# sr42-revB-kbd.net
KiCad netlist of a schematic drawn in EAGLE
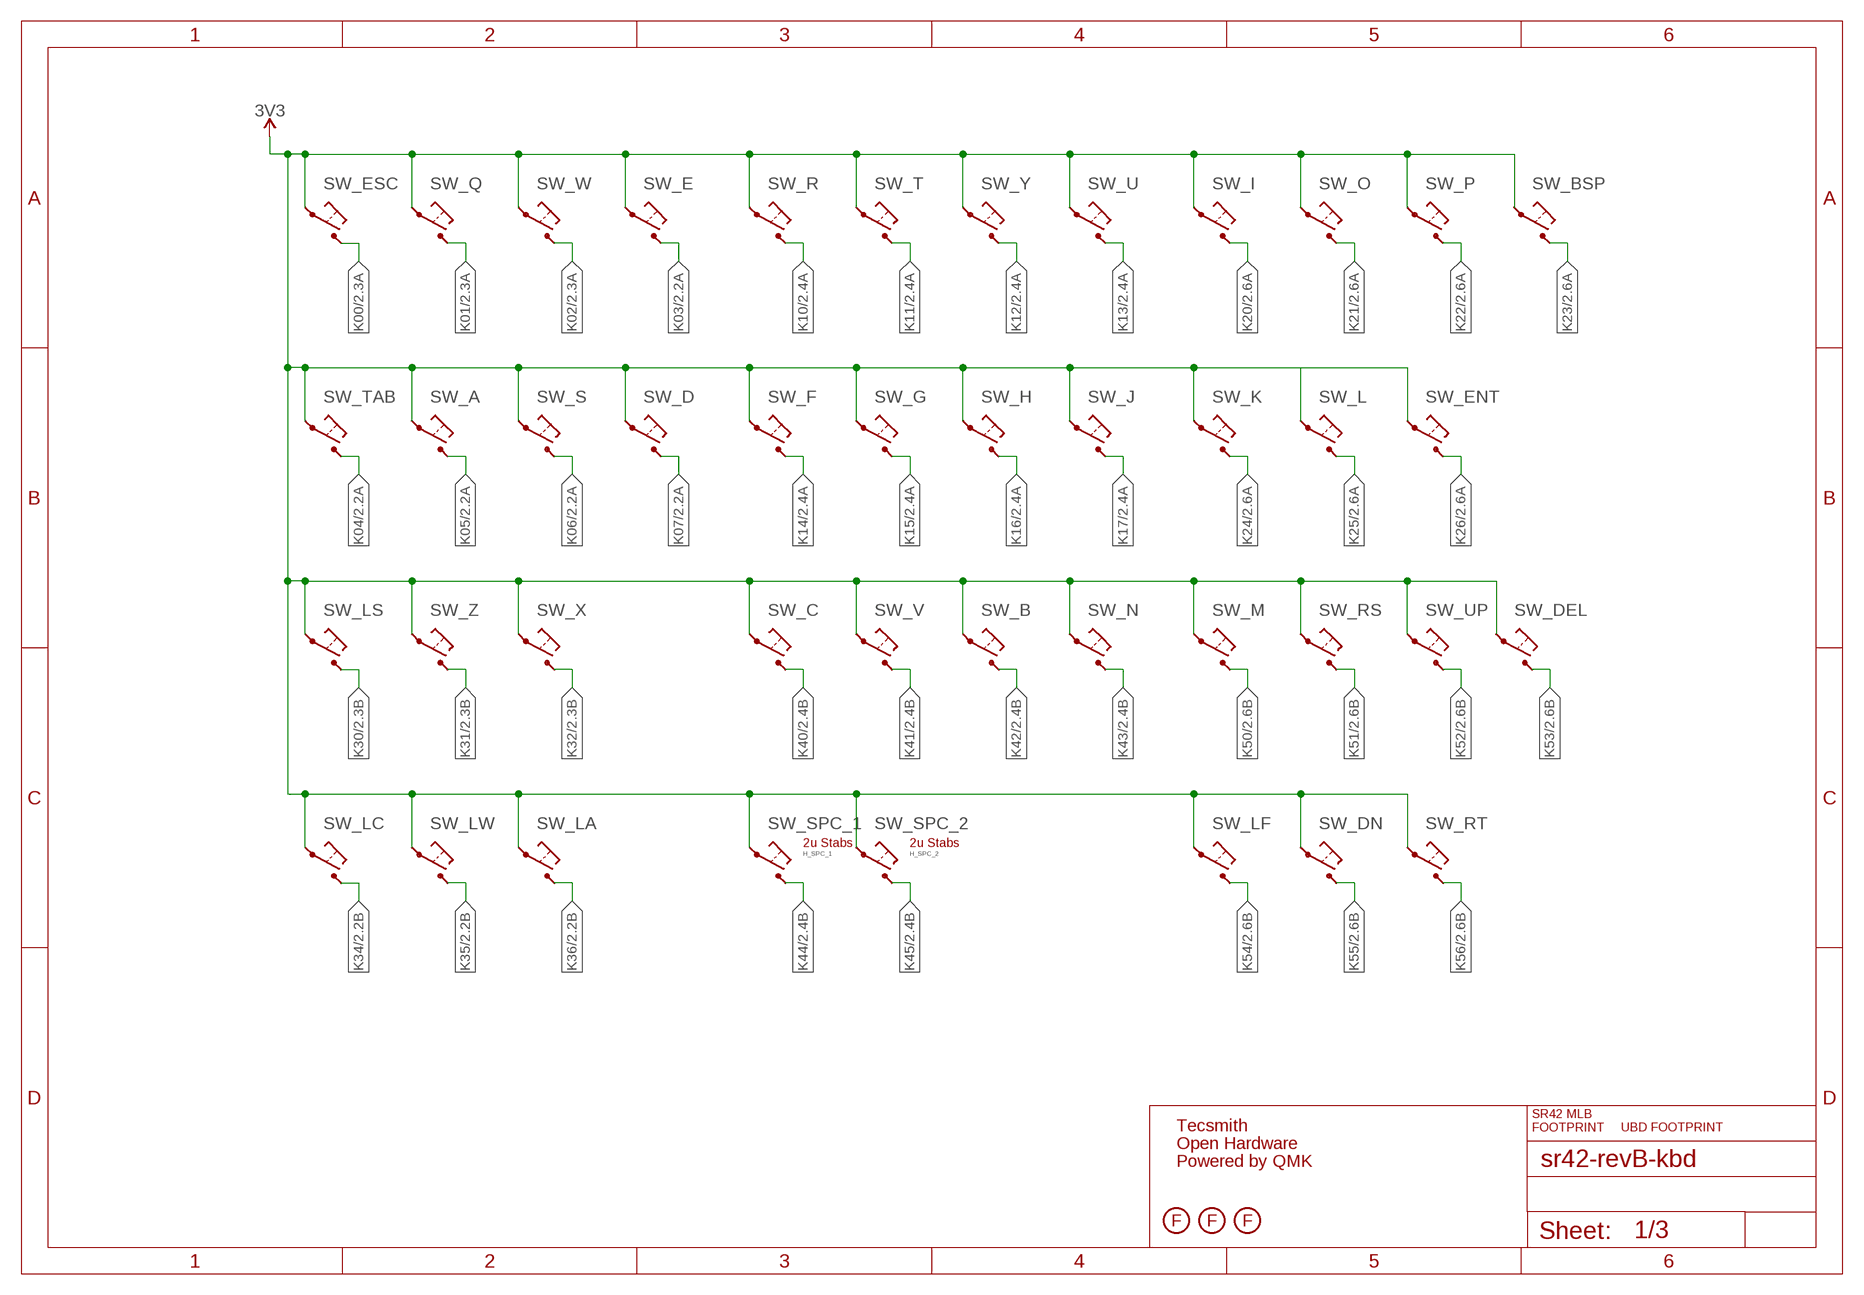
[diagram p0: schematic, sheet 1]
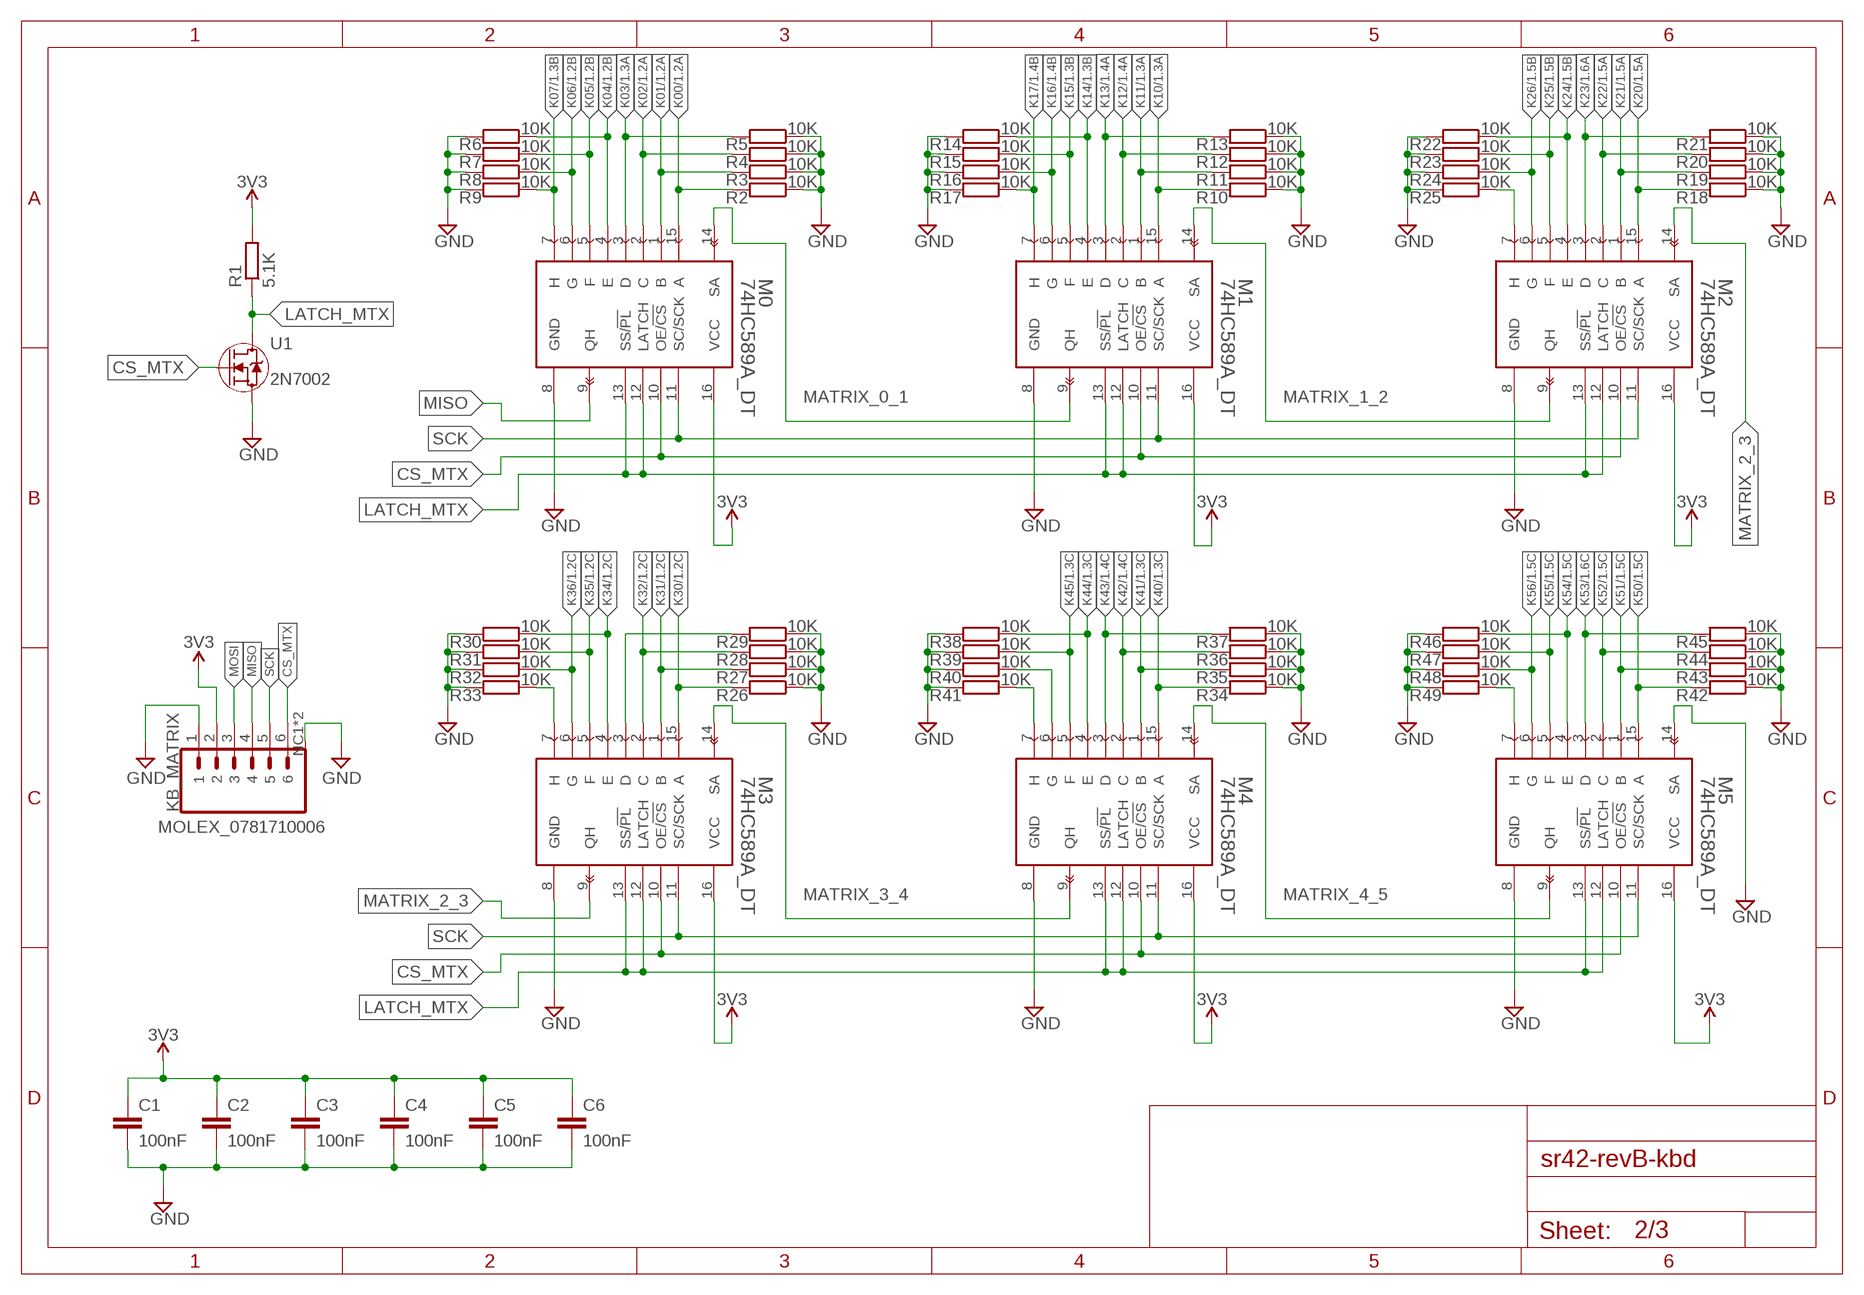
[diagram p1: schematic, sheet 2]
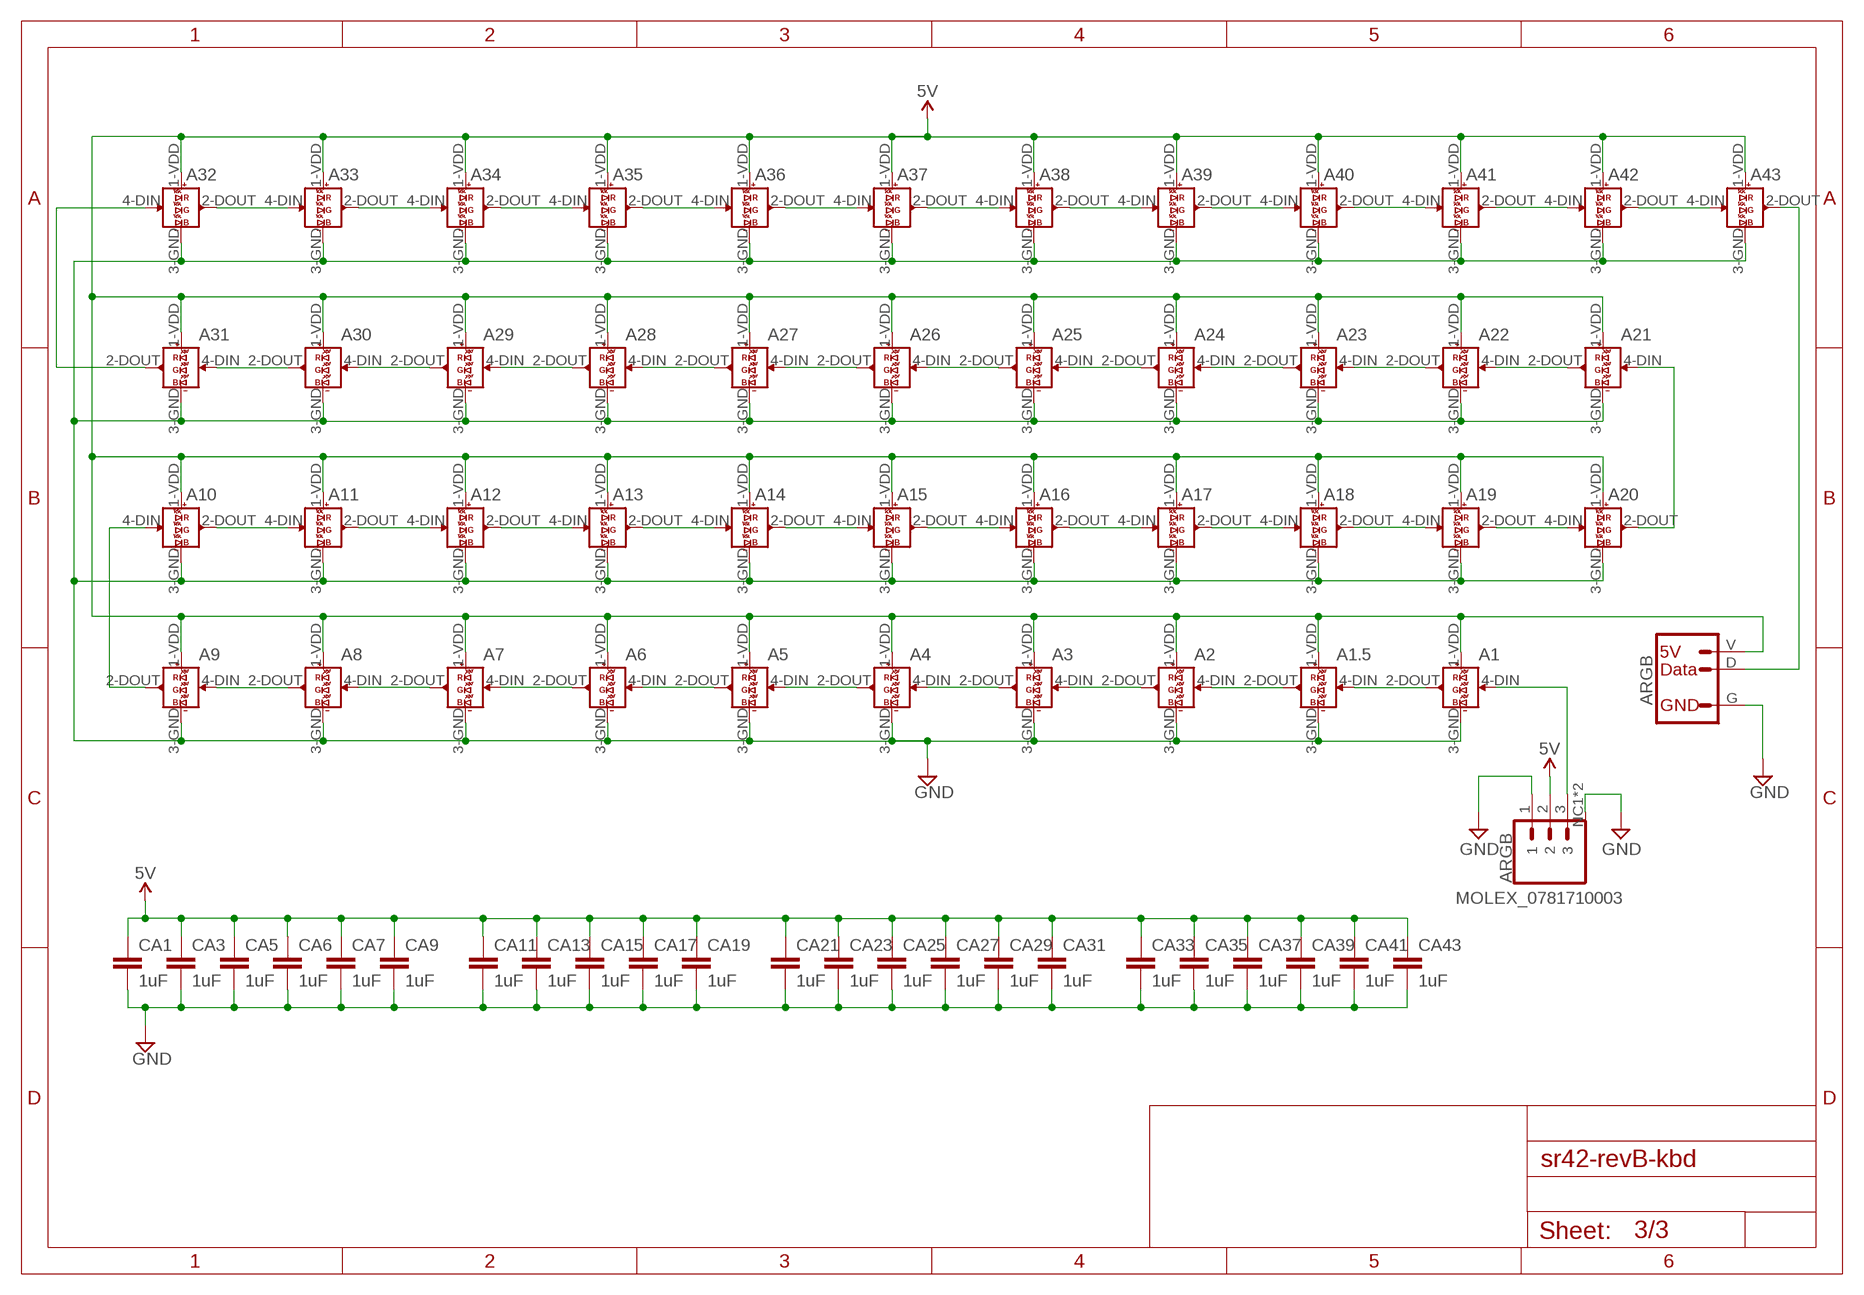
[diagram p2: schematic, sheet 3]

(export (version "E")
  (design (tool "Eeschema 10.0.6"))
  (components
    (comp (ref "A1")
      (value "SK6812-E-REVERSE_V2")
      (footprint "eagle-import:SK6812-E-MILL_V2")
      (libsource (lib "eagle-import") (part "SK6812-E-REVERSE_V2"))
    )
    (comp (ref "A1.5")
      (value "SK6812-E-REVERSE_V2")
      (footprint "eagle-import:SK6812-E-MILL_V2")
      (libsource (lib "eagle-import") (part "SK6812-E-REVERSE_V2"))
    )
    (comp (ref "A2")
      (value "SK6812-E-REVERSE_V2")
      (footprint "eagle-import:SK6812-E-MILL_V2")
      (libsource (lib "eagle-import") (part "SK6812-E-REVERSE_V2"))
    )
    (comp (ref "A3")
      (value "SK6812-E-REVERSE_V2")
      (footprint "eagle-import:SK6812-E-MILL_V2")
      (libsource (lib "eagle-import") (part "SK6812-E-REVERSE_V2"))
    )
    (comp (ref "A4")
      (value "SK6812-E-REVERSE_V2")
      (footprint "eagle-import:SK6812-E-MILL_V2")
      (libsource (lib "eagle-import") (part "SK6812-E-REVERSE_V2"))
    )
    (comp (ref "A5")
      (value "SK6812-E-REVERSE_V2")
      (footprint "eagle-import:SK6812-E-MILL_V2")
      (libsource (lib "eagle-import") (part "SK6812-E-REVERSE_V2"))
    )
    (comp (ref "A6")
      (value "SK6812-E-REVERSE_V2")
      (footprint "eagle-import:SK6812-E-MILL_V2")
      (libsource (lib "eagle-import") (part "SK6812-E-REVERSE_V2"))
    )
    (comp (ref "A7")
      (value "SK6812-E-REVERSE_V2")
      (footprint "eagle-import:SK6812-E-MILL_V2")
      (libsource (lib "eagle-import") (part "SK6812-E-REVERSE_V2"))
    )
    (comp (ref "A8")
      (value "SK6812-E-REVERSE_V2")
      (footprint "eagle-import:SK6812-E-MILL_V2")
      (libsource (lib "eagle-import") (part "SK6812-E-REVERSE_V2"))
    )
    (comp (ref "A9")
      (value "SK6812-E-REVERSE_V2")
      (footprint "eagle-import:SK6812-E-MILL_V2")
      (libsource (lib "eagle-import") (part "SK6812-E-REVERSE_V2"))
    )
    (comp (ref "A10")
      (value "SK6812-E-REVERSE_V2")
      (footprint "eagle-import:SK6812-E-MILL_V2")
      (libsource (lib "eagle-import") (part "SK6812-E-REVERSE_V2"))
    )
    (comp (ref "A11")
      (value "SK6812-E-REVERSE_V2")
      (footprint "eagle-import:SK6812-E-MILL_V2")
      (libsource (lib "eagle-import") (part "SK6812-E-REVERSE_V2"))
    )
    (comp (ref "A12")
      (value "SK6812-E-REVERSE_V2")
      (footprint "eagle-import:SK6812-E-MILL_V2")
      (libsource (lib "eagle-import") (part "SK6812-E-REVERSE_V2"))
    )
    (comp (ref "A13")
      (value "SK6812-E-REVERSE_V2")
      (footprint "eagle-import:SK6812-E-MILL_V2")
      (libsource (lib "eagle-import") (part "SK6812-E-REVERSE_V2"))
    )
    (comp (ref "A14")
      (value "SK6812-E-REVERSE_V2")
      (footprint "eagle-import:SK6812-E-MILL_V2")
      (libsource (lib "eagle-import") (part "SK6812-E-REVERSE_V2"))
    )
    (comp (ref "A15")
      (value "SK6812-E-REVERSE_V2")
      (footprint "eagle-import:SK6812-E-MILL_V2")
      (libsource (lib "eagle-import") (part "SK6812-E-REVERSE_V2"))
    )
    (comp (ref "A16")
      (value "SK6812-E-REVERSE_V2")
      (footprint "eagle-import:SK6812-E-MILL_V2")
      (libsource (lib "eagle-import") (part "SK6812-E-REVERSE_V2"))
    )
    (comp (ref "A17")
      (value "SK6812-E-REVERSE_V2")
      (footprint "eagle-import:SK6812-E-MILL_V2")
      (libsource (lib "eagle-import") (part "SK6812-E-REVERSE_V2"))
    )
    (comp (ref "A18")
      (value "SK6812-E-REVERSE_V2")
      (footprint "eagle-import:SK6812-E-MILL_V2")
      (libsource (lib "eagle-import") (part "SK6812-E-REVERSE_V2"))
    )
    (comp (ref "A19")
      (value "SK6812-E-REVERSE_V2")
      (footprint "eagle-import:SK6812-E-MILL_V2")
      (libsource (lib "eagle-import") (part "SK6812-E-REVERSE_V2"))
    )
    (comp (ref "A20")
      (value "SK6812-E-REVERSE_V2")
      (footprint "eagle-import:SK6812-E-MILL_V2")
      (libsource (lib "eagle-import") (part "SK6812-E-REVERSE_V2"))
    )
    (comp (ref "A21")
      (value "SK6812-E-REVERSE_V2")
      (footprint "eagle-import:SK6812-E-MILL_V2")
      (libsource (lib "eagle-import") (part "SK6812-E-REVERSE_V2"))
    )
    (comp (ref "A22")
      (value "SK6812-E-REVERSE_V2")
      (footprint "eagle-import:SK6812-E-MILL_V2")
      (libsource (lib "eagle-import") (part "SK6812-E-REVERSE_V2"))
    )
    (comp (ref "A23")
      (value "SK6812-E-REVERSE_V2")
      (footprint "eagle-import:SK6812-E-MILL_V2")
      (libsource (lib "eagle-import") (part "SK6812-E-REVERSE_V2"))
    )
    (comp (ref "A24")
      (value "SK6812-E-REVERSE_V2")
      (footprint "eagle-import:SK6812-E-MILL_V2")
      (libsource (lib "eagle-import") (part "SK6812-E-REVERSE_V2"))
    )
    (comp (ref "A25")
      (value "SK6812-E-REVERSE_V2")
      (footprint "eagle-import:SK6812-E-MILL_V2")
      (libsource (lib "eagle-import") (part "SK6812-E-REVERSE_V2"))
    )
    (comp (ref "A26")
      (value "SK6812-E-REVERSE_V2")
      (footprint "eagle-import:SK6812-E-MILL_V2")
      (libsource (lib "eagle-import") (part "SK6812-E-REVERSE_V2"))
    )
    (comp (ref "A27")
      (value "SK6812-E-REVERSE_V2")
      (footprint "eagle-import:SK6812-E-MILL_V2")
      (libsource (lib "eagle-import") (part "SK6812-E-REVERSE_V2"))
    )
    (comp (ref "A28")
      (value "SK6812-E-REVERSE_V2")
      (footprint "eagle-import:SK6812-E-MILL_V2")
      (libsource (lib "eagle-import") (part "SK6812-E-REVERSE_V2"))
    )
    (comp (ref "A29")
      (value "SK6812-E-REVERSE_V2")
      (footprint "eagle-import:SK6812-E-MILL_V2")
      (libsource (lib "eagle-import") (part "SK6812-E-REVERSE_V2"))
    )
    (comp (ref "A30")
      (value "SK6812-E-REVERSE_V2")
      (footprint "eagle-import:SK6812-E-MILL_V2")
      (libsource (lib "eagle-import") (part "SK6812-E-REVERSE_V2"))
    )
    (comp (ref "A31")
      (value "SK6812-E-REVERSE_V2")
      (footprint "eagle-import:SK6812-E-MILL_V2")
      (libsource (lib "eagle-import") (part "SK6812-E-REVERSE_V2"))
    )
    (comp (ref "A32")
      (value "SK6812-E-REVERSE_V2")
      (footprint "eagle-import:SK6812-E-MILL_V2")
      (libsource (lib "eagle-import") (part "SK6812-E-REVERSE_V2"))
    )
    (comp (ref "A33")
      (value "SK6812-E-REVERSE_V2")
      (footprint "eagle-import:SK6812-E-MILL_V2")
      (libsource (lib "eagle-import") (part "SK6812-E-REVERSE_V2"))
    )
    (comp (ref "A34")
      (value "SK6812-E-REVERSE_V2")
      (footprint "eagle-import:SK6812-E-MILL_V2")
      (libsource (lib "eagle-import") (part "SK6812-E-REVERSE_V2"))
    )
    (comp (ref "A35")
      (value "SK6812-E-REVERSE_V2")
      (footprint "eagle-import:SK6812-E-MILL_V2")
      (libsource (lib "eagle-import") (part "SK6812-E-REVERSE_V2"))
    )
    (comp (ref "A36")
      (value "SK6812-E-REVERSE_V2")
      (footprint "eagle-import:SK6812-E-MILL_V2")
      (libsource (lib "eagle-import") (part "SK6812-E-REVERSE_V2"))
    )
    (comp (ref "A37")
      (value "SK6812-E-REVERSE_V2")
      (footprint "eagle-import:SK6812-E-MILL_V2")
      (libsource (lib "eagle-import") (part "SK6812-E-REVERSE_V2"))
    )
    (comp (ref "A38")
      (value "SK6812-E-REVERSE_V2")
      (footprint "eagle-import:SK6812-E-MILL_V2")
      (libsource (lib "eagle-import") (part "SK6812-E-REVERSE_V2"))
    )
    (comp (ref "A39")
      (value "SK6812-E-REVERSE_V2")
      (footprint "eagle-import:SK6812-E-MILL_V2")
      (libsource (lib "eagle-import") (part "SK6812-E-REVERSE_V2"))
    )
    (comp (ref "A40")
      (value "SK6812-E-REVERSE_V2")
      (footprint "eagle-import:SK6812-E-MILL_V2")
      (libsource (lib "eagle-import") (part "SK6812-E-REVERSE_V2"))
    )
    (comp (ref "A41")
      (value "SK6812-E-REVERSE_V2")
      (footprint "eagle-import:SK6812-E-MILL_V2")
      (libsource (lib "eagle-import") (part "SK6812-E-REVERSE_V2"))
    )
    (comp (ref "A42")
      (value "SK6812-E-REVERSE_V2")
      (footprint "eagle-import:SK6812-E-MILL_V2")
      (libsource (lib "eagle-import") (part "SK6812-E-REVERSE_V2"))
    )
    (comp (ref "A43")
      (value "SK6812-E-REVERSE_V2")
      (footprint "eagle-import:SK6812-E-MILL_V2")
      (libsource (lib "eagle-import") (part "SK6812-E-REVERSE_V2"))
    )
    (comp (ref "ARGB")
      (value "MOLEX_0781710003")
      (footprint "eagle-import:MOLEX_781710003")
      (libsource (lib "eagle-import") (part "MOLEX_0781710003"))
    )
    (comp (ref "CA1")
      (value "1uF")
      (footprint "eagle-import:C0603")
      (libsource (lib "eagle-import") (part "C-EUC0603"))
    )
    (comp (ref "CA3")
      (value "1uF")
      (footprint "eagle-import:C0603")
      (libsource (lib "eagle-import") (part "C-EUC0603"))
    )
    (comp (ref "CA5")
      (value "1uF")
      (footprint "eagle-import:C0603")
      (libsource (lib "eagle-import") (part "C-EUC0603"))
    )
    (comp (ref "CA6")
      (value "1uF")
      (footprint "eagle-import:C0603")
      (libsource (lib "eagle-import") (part "C-EUC0603"))
    )
    (comp (ref "CA7")
      (value "1uF")
      (footprint "eagle-import:C0603")
      (libsource (lib "eagle-import") (part "C-EUC0603"))
    )
    (comp (ref "CA9")
      (value "1uF")
      (footprint "eagle-import:C0603")
      (libsource (lib "eagle-import") (part "C-EUC0603"))
    )
    (comp (ref "CA11")
      (value "1uF")
      (footprint "eagle-import:C0603")
      (libsource (lib "eagle-import") (part "C-EUC0603"))
    )
    (comp (ref "CA13")
      (value "1uF")
      (footprint "eagle-import:C0603")
      (libsource (lib "eagle-import") (part "C-EUC0603"))
    )
    (comp (ref "CA15")
      (value "1uF")
      (footprint "eagle-import:C0603")
      (libsource (lib "eagle-import") (part "C-EUC0603"))
    )
    (comp (ref "CA17")
      (value "1uF")
      (footprint "eagle-import:C0603")
      (libsource (lib "eagle-import") (part "C-EUC0603"))
    )
    (comp (ref "CA19")
      (value "1uF")
      (footprint "eagle-import:C0603")
      (libsource (lib "eagle-import") (part "C-EUC0603"))
    )
    (comp (ref "CA21")
      (value "1uF")
      (footprint "eagle-import:C0603")
      (libsource (lib "eagle-import") (part "C-EUC0603"))
    )
    (comp (ref "CA23")
      (value "1uF")
      (footprint "eagle-import:C0603")
      (libsource (lib "eagle-import") (part "C-EUC0603"))
    )
    (comp (ref "CA25")
      (value "1uF")
      (footprint "eagle-import:C0603")
      (libsource (lib "eagle-import") (part "C-EUC0603"))
    )
    (comp (ref "CA27")
      (value "1uF")
      (footprint "eagle-import:C0603")
      (libsource (lib "eagle-import") (part "C-EUC0603"))
    )
    (comp (ref "CA29")
      (value "1uF")
      (footprint "eagle-import:C0603")
      (libsource (lib "eagle-import") (part "C-EUC0603"))
    )
    (comp (ref "CA31")
      (value "1uF")
      (footprint "eagle-import:C0603")
      (libsource (lib "eagle-import") (part "C-EUC0603"))
    )
    (comp (ref "CA33")
      (value "1uF")
      (footprint "eagle-import:C0603")
      (libsource (lib "eagle-import") (part "C-EUC0603"))
    )
    (comp (ref "CA35")
      (value "1uF")
      (footprint "eagle-import:C0603")
      (libsource (lib "eagle-import") (part "C-EUC0603"))
    )
    (comp (ref "CA37")
      (value "1uF")
      (footprint "eagle-import:C0603")
      (libsource (lib "eagle-import") (part "C-EUC0603"))
    )
    (comp (ref "CA39")
      (value "1uF")
      (footprint "eagle-import:C0603")
      (libsource (lib "eagle-import") (part "C-EUC0603"))
    )
    (comp (ref "CA41")
      (value "1uF")
      (footprint "eagle-import:C0603")
      (libsource (lib "eagle-import") (part "C-EUC0603"))
    )
    (comp (ref "CA43")
      (value "1uF")
      (footprint "eagle-import:C0603")
      (libsource (lib "eagle-import") (part "C-EUC0603"))
    )
    (comp (ref "I44")
      (value "ARGB")
      (footprint "eagle-import:ARGB")
      (libsource (lib "eagle-import") (part "ARGB"))
    )
    (comp (ref "H_SPC_1")
      (value "MX-STABS-200U")
      (footprint "eagle-import:MX-STABS-200U")
      (libsource (lib "eagle-import") (part "MX-STABS-200U"))
    )
    (comp (ref "H_SPC_2")
      (value "MX-STABS-200U")
      (footprint "eagle-import:MX-STABS-200U")
      (libsource (lib "eagle-import") (part "MX-STABS-200U"))
    )
    (comp (ref "LOGO1")
      (value "OSHW-LOGOL")
      (footprint "eagle-import:OSHW-LOGO-L")
      (libsource (lib "eagle-import") (part "OSHW-LOGOL"))
    )
    (comp (ref "SW_A")
      (value "MX-5-PIN-HOTSWAP-PAD")
      (footprint "eagle-import:MX-5-PIN-HOTSWAP-PAD")
      (libsource (lib "eagle-import") (part "MX-5-PIN-HOTSWAP-PAD"))
    )
    (comp (ref "SW_B")
      (value "MX-5-PIN-HOTSWAP-PAD")
      (footprint "eagle-import:MX-5-PIN-HOTSWAP-PAD")
      (libsource (lib "eagle-import") (part "MX-5-PIN-HOTSWAP-PAD"))
    )
    (comp (ref "SW_BSP")
      (value "MX-5-PIN-HOTSWAP-PAD")
      (footprint "eagle-import:MX-5-PIN-HOTSWAP-PAD")
      (libsource (lib "eagle-import") (part "MX-5-PIN-HOTSWAP-PAD"))
    )
    (comp (ref "SW_C")
      (value "MX-5-PIN-HOTSWAP-PAD")
      (footprint "eagle-import:MX-5-PIN-HOTSWAP-PAD")
      (libsource (lib "eagle-import") (part "MX-5-PIN-HOTSWAP-PAD"))
    )
    (comp (ref "SW_D")
      (value "MX-5-PIN-HOTSWAP-PAD")
      (footprint "eagle-import:MX-5-PIN-HOTSWAP-PAD")
      (libsource (lib "eagle-import") (part "MX-5-PIN-HOTSWAP-PAD"))
    )
    (comp (ref "SW_DEL")
      (value "MX-5-PIN-HOTSWAP-PAD")
      (footprint "eagle-import:MX-5-PIN-HOTSWAP-PAD")
      (libsource (lib "eagle-import") (part "MX-5-PIN-HOTSWAP-PAD"))
    )
    (comp (ref "SW_DN")
      (value "MX-5-PIN-HOTSWAP-PAD")
      (footprint "eagle-import:MX-5-PIN-HOTSWAP-PAD")
      (libsource (lib "eagle-import") (part "MX-5-PIN-HOTSWAP-PAD"))
    )
    (comp (ref "SW_E")
      (value "MX-5-PIN-HOTSWAP-PAD")
      (footprint "eagle-import:MX-5-PIN-HOTSWAP-PAD")
      (libsource (lib "eagle-import") (part "MX-5-PIN-HOTSWAP-PAD"))
    )
    (comp (ref "SW_ENT")
      (value "MX-5-PIN-HOTSWAP-PAD")
      (footprint "eagle-import:MX-5-PIN-HOTSWAP-PAD")
      (libsource (lib "eagle-import") (part "MX-5-PIN-HOTSWAP-PAD"))
    )
    (comp (ref "SW_ESC")
      (value "MX-5-PIN-HOTSWAP-PAD")
      (footprint "eagle-import:MX-5-PIN-HOTSWAP-PAD")
      (libsource (lib "eagle-import") (part "MX-5-PIN-HOTSWAP-PAD"))
    )
    (comp (ref "SW_F")
      (value "MX-5-PIN-HOTSWAP-PAD")
      (footprint "eagle-import:MX-5-PIN-HOTSWAP-PAD")
      (libsource (lib "eagle-import") (part "MX-5-PIN-HOTSWAP-PAD"))
    )
    (comp (ref "SW_G")
      (value "MX-5-PIN-HOTSWAP-PAD")
      (footprint "eagle-import:MX-5-PIN-HOTSWAP-PAD")
      (libsource (lib "eagle-import") (part "MX-5-PIN-HOTSWAP-PAD"))
    )
    (comp (ref "SW_H")
      (value "MX-5-PIN-HOTSWAP-PAD")
      (footprint "eagle-import:MX-5-PIN-HOTSWAP-PAD")
      (libsource (lib "eagle-import") (part "MX-5-PIN-HOTSWAP-PAD"))
    )
    (comp (ref "SW_I")
      (value "MX-5-PIN-HOTSWAP-PAD")
      (footprint "eagle-import:MX-5-PIN-HOTSWAP-PAD")
      (libsource (lib "eagle-import") (part "MX-5-PIN-HOTSWAP-PAD"))
    )
    (comp (ref "SW_J")
      (value "MX-5-PIN-HOTSWAP-PAD")
      (footprint "eagle-import:MX-5-PIN-HOTSWAP-PAD")
      (libsource (lib "eagle-import") (part "MX-5-PIN-HOTSWAP-PAD"))
    )
    (comp (ref "SW_K")
      (value "MX-5-PIN-HOTSWAP-PAD")
      (footprint "eagle-import:MX-5-PIN-HOTSWAP-PAD")
      (libsource (lib "eagle-import") (part "MX-5-PIN-HOTSWAP-PAD"))
    )
    (comp (ref "SW_L")
      (value "MX-5-PIN-HOTSWAP-PAD")
      (footprint "eagle-import:MX-5-PIN-HOTSWAP-PAD")
      (libsource (lib "eagle-import") (part "MX-5-PIN-HOTSWAP-PAD"))
    )
    (comp (ref "SW_LA")
      (value "MX-5-PIN-HOTSWAP-PAD")
      (footprint "eagle-import:MX-5-PIN-HOTSWAP-PAD")
      (libsource (lib "eagle-import") (part "MX-5-PIN-HOTSWAP-PAD"))
    )
    (comp (ref "SW_LC")
      (value "MX-5-PIN-HOTSWAP-PAD")
      (footprint "eagle-import:MX-5-PIN-HOTSWAP-PAD")
      (libsource (lib "eagle-import") (part "MX-5-PIN-HOTSWAP-PAD"))
    )
    (comp (ref "SW_LF")
      (value "MX-5-PIN-HOTSWAP-PAD")
      (footprint "eagle-import:MX-5-PIN-HOTSWAP-PAD")
      (libsource (lib "eagle-import") (part "MX-5-PIN-HOTSWAP-PAD"))
    )
    (comp (ref "SW_LS")
      (value "MX-5-PIN-HOTSWAP-PAD")
      (footprint "eagle-import:MX-5-PIN-HOTSWAP-PAD")
      (libsource (lib "eagle-import") (part "MX-5-PIN-HOTSWAP-PAD"))
    )
    (comp (ref "SW_LW")
      (value "MX-5-PIN-HOTSWAP-PAD")
      (footprint "eagle-import:MX-5-PIN-HOTSWAP-PAD")
      (libsource (lib "eagle-import") (part "MX-5-PIN-HOTSWAP-PAD"))
    )
    (comp (ref "SW_M")
      (value "MX-5-PIN-HOTSWAP-PAD")
      (footprint "eagle-import:MX-5-PIN-HOTSWAP-PAD")
      (libsource (lib "eagle-import") (part "MX-5-PIN-HOTSWAP-PAD"))
    )
    (comp (ref "SW_N")
      (value "MX-5-PIN-HOTSWAP-PAD")
      (footprint "eagle-import:MX-5-PIN-HOTSWAP-PAD")
      (libsource (lib "eagle-import") (part "MX-5-PIN-HOTSWAP-PAD"))
    )
    (comp (ref "SW_O")
      (value "MX-5-PIN-HOTSWAP-PAD")
      (footprint "eagle-import:MX-5-PIN-HOTSWAP-PAD")
      (libsource (lib "eagle-import") (part "MX-5-PIN-HOTSWAP-PAD"))
    )
    (comp (ref "SW_P")
      (value "MX-5-PIN-HOTSWAP-PAD")
      (footprint "eagle-import:MX-5-PIN-HOTSWAP-PAD")
      (libsource (lib "eagle-import") (part "MX-5-PIN-HOTSWAP-PAD"))
    )
    (comp (ref "SW_Q")
      (value "MX-5-PIN-HOTSWAP-PAD")
      (footprint "eagle-import:MX-5-PIN-HOTSWAP-PAD")
      (libsource (lib "eagle-import") (part "MX-5-PIN-HOTSWAP-PAD"))
    )
    (comp (ref "SW_R")
      (value "MX-5-PIN-HOTSWAP-PAD")
      (footprint "eagle-import:MX-5-PIN-HOTSWAP-PAD")
      (libsource (lib "eagle-import") (part "MX-5-PIN-HOTSWAP-PAD"))
    )
    (comp (ref "SW_RS")
      (value "MX-5-PIN-HOTSWAP-PAD")
      (footprint "eagle-import:MX-5-PIN-HOTSWAP-PAD")
      (libsource (lib "eagle-import") (part "MX-5-PIN-HOTSWAP-PAD"))
    )
    (comp (ref "SW_RT")
      (value "MX-5-PIN-HOTSWAP-PAD")
      (footprint "eagle-import:MX-5-PIN-HOTSWAP-PAD")
      (libsource (lib "eagle-import") (part "MX-5-PIN-HOTSWAP-PAD"))
    )
    (comp (ref "SW_S")
      (value "MX-5-PIN-HOTSWAP-PAD")
      (footprint "eagle-import:MX-5-PIN-HOTSWAP-PAD")
      (libsource (lib "eagle-import") (part "MX-5-PIN-HOTSWAP-PAD"))
    )
    (comp (ref "SW_SPC_1")
      (value "MX-5-PIN-HOTSWAP-PAD")
      (footprint "eagle-import:MX-5-PIN-HOTSWAP-PAD")
      (libsource (lib "eagle-import") (part "MX-5-PIN-HOTSWAP-PAD"))
    )
    (comp (ref "SW_SPC_2")
      (value "MX-5-PIN-HOTSWAP-PAD")
      (footprint "eagle-import:MX-5-PIN-HOTSWAP-PAD")
      (libsource (lib "eagle-import") (part "MX-5-PIN-HOTSWAP-PAD"))
    )
    (comp (ref "SW_T")
      (value "MX-5-PIN-HOTSWAP-PAD")
      (footprint "eagle-import:MX-5-PIN-HOTSWAP-PAD")
      (libsource (lib "eagle-import") (part "MX-5-PIN-HOTSWAP-PAD"))
    )
    (comp (ref "SW_TAB")
      (value "MX-5-PIN-HOTSWAP-PAD")
      (footprint "eagle-import:MX-5-PIN-HOTSWAP-PAD")
      (libsource (lib "eagle-import") (part "MX-5-PIN-HOTSWAP-PAD"))
    )
    (comp (ref "SW_U")
      (value "MX-5-PIN-HOTSWAP-PAD")
      (footprint "eagle-import:MX-5-PIN-HOTSWAP-PAD")
      (libsource (lib "eagle-import") (part "MX-5-PIN-HOTSWAP-PAD"))
    )
    (comp (ref "SW_UP")
      (value "MX-5-PIN-HOTSWAP-PAD")
      (footprint "eagle-import:MX-5-PIN-HOTSWAP-PAD")
      (libsource (lib "eagle-import") (part "MX-5-PIN-HOTSWAP-PAD"))
    )
    (comp (ref "SW_V")
      (value "MX-5-PIN-HOTSWAP-PAD")
      (footprint "eagle-import:MX-5-PIN-HOTSWAP-PAD")
      (libsource (lib "eagle-import") (part "MX-5-PIN-HOTSWAP-PAD"))
    )
    (comp (ref "SW_W")
      (value "MX-5-PIN-HOTSWAP-PAD")
      (footprint "eagle-import:MX-5-PIN-HOTSWAP-PAD")
      (libsource (lib "eagle-import") (part "MX-5-PIN-HOTSWAP-PAD"))
    )
    (comp (ref "SW_X")
      (value "MX-5-PIN-HOTSWAP-PAD")
      (footprint "eagle-import:MX-5-PIN-HOTSWAP-PAD")
      (libsource (lib "eagle-import") (part "MX-5-PIN-HOTSWAP-PAD"))
    )
    (comp (ref "SW_Y")
      (value "MX-5-PIN-HOTSWAP-PAD")
      (footprint "eagle-import:MX-5-PIN-HOTSWAP-PAD")
      (libsource (lib "eagle-import") (part "MX-5-PIN-HOTSWAP-PAD"))
    )
    (comp (ref "SW_Z")
      (value "MX-5-PIN-HOTSWAP-PAD")
      (footprint "eagle-import:MX-5-PIN-HOTSWAP-PAD")
      (libsource (lib "eagle-import") (part "MX-5-PIN-HOTSWAP-PAD"))
    )
    (comp (ref "U$1")
      (value "SR42_MLB_FOOTPRINT")
      (footprint "eagle-import:SR42_MLB_FOOTPRINT")
      (libsource (lib "eagle-import") (part "SR42_MLB_FOOTPRINT"))
    )
    (comp (ref "U$2")
      (value "UBD_FOOTPRINT")
      (footprint "eagle-import:UDB_FOOTPRINT")
      (libsource (lib "eagle-import") (part "UBD_FOOTPRINT"))
    )
    (comp (ref "U$3")
      (value "TECSMITH-LOGOLONG")
      (footprint "eagle-import:TECSMITH-NAME")
      (libsource (lib "eagle-import") (part "TECSMITH-LOGOLONG"))
    )
    (comp (ref "U$4")
      (value "QMK_LOGO")
      (footprint "eagle-import:QMK_LOGO")
      (libsource (lib "eagle-import") (part "QMK_LOGO"))
    )
    (comp (ref "U$5")
      (value "FIDUCIAL")
      (footprint "eagle-import:FIDUCIAL")
      (libsource (lib "eagle-import") (part "FIDUCIAL"))
    )
    (comp (ref "U$6")
      (value "FIDUCIAL")
      (footprint "eagle-import:FIDUCIAL")
      (libsource (lib "eagle-import") (part "FIDUCIAL"))
    )
    (comp (ref "U$7")
      (value "FIDUCIAL")
      (footprint "eagle-import:FIDUCIAL")
      (libsource (lib "eagle-import") (part "FIDUCIAL"))
    )
    (comp (ref "C1")
      (value "100nF")
      (footprint "eagle-import:C0603")
      (libsource (lib "eagle-import") (part "C-EUC0603"))
    )
    (comp (ref "C2")
      (value "100nF")
      (footprint "eagle-import:C0603")
      (libsource (lib "eagle-import") (part "C-EUC0603"))
    )
    (comp (ref "C3")
      (value "100nF")
      (footprint "eagle-import:C0603")
      (libsource (lib "eagle-import") (part "C-EUC0603"))
    )
    (comp (ref "C4")
      (value "100nF")
      (footprint "eagle-import:C0603")
      (libsource (lib "eagle-import") (part "C-EUC0603"))
    )
    (comp (ref "C5")
      (value "100nF")
      (footprint "eagle-import:C0603")
      (libsource (lib "eagle-import") (part "C-EUC0603"))
    )
    (comp (ref "C6")
      (value "100nF")
      (footprint "eagle-import:C0603")
      (libsource (lib "eagle-import") (part "C-EUC0603"))
    )
    (comp (ref "KB_MATRIX")
      (value "MOLEX_0781710006")
      (footprint "eagle-import:MOLEX_781710006")
      (libsource (lib "eagle-import") (part "MOLEX_0781710006"))
    )
    (comp (ref "M0")
      (value "74HC589A_DT")
      (footprint "eagle-import:TSSOP16")
      (libsource (lib "eagle-import") (part "74HC589A_DT"))
    )
    (comp (ref "M1")
      (value "74HC589A_DT")
      (footprint "eagle-import:TSSOP16")
      (libsource (lib "eagle-import") (part "74HC589A_DT"))
    )
    (comp (ref "M2")
      (value "74HC589A_DT")
      (footprint "eagle-import:TSSOP16")
      (libsource (lib "eagle-import") (part "74HC589A_DT"))
    )
    (comp (ref "M3")
      (value "74HC589A_DT")
      (footprint "eagle-import:TSSOP16")
      (libsource (lib "eagle-import") (part "74HC589A_DT"))
    )
    (comp (ref "M4")
      (value "74HC589A_DT")
      (footprint "eagle-import:TSSOP16")
      (libsource (lib "eagle-import") (part "74HC589A_DT"))
    )
    (comp (ref "M5")
      (value "74HC589A_DT")
      (footprint "eagle-import:TSSOP16")
      (libsource (lib "eagle-import") (part "74HC589A_DT"))
    )
    (comp (ref "R1")
      (value "5.1K")
      (footprint "eagle-import:R0603")
      (libsource (lib "eagle-import") (part "R-EU_R0603"))
    )
    (comp (ref "R2")
      (value "10K")
      (footprint "eagle-import:R0603")
      (libsource (lib "eagle-import") (part "R-EU_R0603"))
    )
    (comp (ref "R3")
      (value "10K")
      (footprint "eagle-import:R0603")
      (libsource (lib "eagle-import") (part "R-EU_R0603"))
    )
    (comp (ref "R4")
      (value "10K")
      (footprint "eagle-import:R0603")
      (libsource (lib "eagle-import") (part "R-EU_R0603"))
    )
    (comp (ref "R5")
      (value "10K")
      (footprint "eagle-import:R0603")
      (libsource (lib "eagle-import") (part "R-EU_R0603"))
    )
    (comp (ref "R6")
      (value "10K")
      (footprint "eagle-import:R0603")
      (libsource (lib "eagle-import") (part "R-EU_R0603"))
    )
    (comp (ref "R7")
      (value "10K")
      (footprint "eagle-import:R0603")
      (libsource (lib "eagle-import") (part "R-EU_R0603"))
    )
    (comp (ref "R8")
      (value "10K")
      (footprint "eagle-import:R0603")
      (libsource (lib "eagle-import") (part "R-EU_R0603"))
    )
    (comp (ref "R9")
      (value "10K")
      (footprint "eagle-import:R0603")
      (libsource (lib "eagle-import") (part "R-EU_R0603"))
    )
    (comp (ref "R10")
      (value "10K")
      (footprint "eagle-import:R0603")
      (libsource (lib "eagle-import") (part "R-EU_R0603"))
    )
    (comp (ref "R11")
      (value "10K")
      (footprint "eagle-import:R0603")
      (libsource (lib "eagle-import") (part "R-EU_R0603"))
    )
    (comp (ref "R12")
      (value "10K")
      (footprint "eagle-import:R0603")
      (libsource (lib "eagle-import") (part "R-EU_R0603"))
    )
    (comp (ref "R13")
      (value "10K")
      (footprint "eagle-import:R0603")
      (libsource (lib "eagle-import") (part "R-EU_R0603"))
    )
    (comp (ref "R14")
      (value "10K")
      (footprint "eagle-import:R0603")
      (libsource (lib "eagle-import") (part "R-EU_R0603"))
    )
    (comp (ref "R15")
      (value "10K")
      (footprint "eagle-import:R0603")
      (libsource (lib "eagle-import") (part "R-EU_R0603"))
    )
    (comp (ref "R16")
      (value "10K")
      (footprint "eagle-import:R0603")
      (libsource (lib "eagle-import") (part "R-EU_R0603"))
    )
    (comp (ref "R17")
      (value "10K")
      (footprint "eagle-import:R0603")
      (libsource (lib "eagle-import") (part "R-EU_R0603"))
    )
    (comp (ref "R18")
      (value "10K")
      (footprint "eagle-import:R0603")
      (libsource (lib "eagle-import") (part "R-EU_R0603"))
    )
    (comp (ref "R19")
      (value "10K")
      (footprint "eagle-import:R0603")
      (libsource (lib "eagle-import") (part "R-EU_R0603"))
    )
    (comp (ref "R20")
      (value "10K")
      (footprint "eagle-import:R0603")
      (libsource (lib "eagle-import") (part "R-EU_R0603"))
    )
    (comp (ref "R21")
      (value "10K")
      (footprint "eagle-import:R0603")
      (libsource (lib "eagle-import") (part "R-EU_R0603"))
    )
    (comp (ref "R22")
      (value "10K")
      (footprint "eagle-import:R0603")
      (libsource (lib "eagle-import") (part "R-EU_R0603"))
    )
    (comp (ref "R23")
      (value "10K")
      (footprint "eagle-import:R0603")
      (libsource (lib "eagle-import") (part "R-EU_R0603"))
    )
    (comp (ref "R24")
      (value "10K")
      (footprint "eagle-import:R0603")
      (libsource (lib "eagle-import") (part "R-EU_R0603"))
    )
    (comp (ref "R25")
      (value "10K")
      (footprint "eagle-import:R0603")
      (libsource (lib "eagle-import") (part "R-EU_R0603"))
    )
    (comp (ref "R26")
      (value "10K")
      (footprint "eagle-import:R0603")
      (libsource (lib "eagle-import") (part "R-EU_R0603"))
    )
    (comp (ref "R27")
      (value "10K")
      (footprint "eagle-import:R0603")
      (libsource (lib "eagle-import") (part "R-EU_R0603"))
    )
    (comp (ref "R28")
      (value "10K")
      (footprint "eagle-import:R0603")
      (libsource (lib "eagle-import") (part "R-EU_R0603"))
    )
    (comp (ref "R29")
      (value "10K")
      (footprint "eagle-import:R0603")
      (libsource (lib "eagle-import") (part "R-EU_R0603"))
    )
    (comp (ref "R30")
      (value "10K")
      (footprint "eagle-import:R0603")
      (libsource (lib "eagle-import") (part "R-EU_R0603"))
    )
    (comp (ref "R31")
      (value "10K")
      (footprint "eagle-import:R0603")
      (libsource (lib "eagle-import") (part "R-EU_R0603"))
    )
    (comp (ref "R32")
      (value "10K")
      (footprint "eagle-import:R0603")
      (libsource (lib "eagle-import") (part "R-EU_R0603"))
    )
    (comp (ref "R33")
      (value "10K")
      (footprint "eagle-import:R0603")
      (libsource (lib "eagle-import") (part "R-EU_R0603"))
    )
    (comp (ref "R34")
      (value "10K")
      (footprint "eagle-import:R0603")
      (libsource (lib "eagle-import") (part "R-EU_R0603"))
    )
    (comp (ref "R35")
      (value "10K")
      (footprint "eagle-import:R0603")
      (libsource (lib "eagle-import") (part "R-EU_R0603"))
    )
    (comp (ref "R36")
      (value "10K")
      (footprint "eagle-import:R0603")
      (libsource (lib "eagle-import") (part "R-EU_R0603"))
    )
    (comp (ref "R37")
      (value "10K")
      (footprint "eagle-import:R0603")
      (libsource (lib "eagle-import") (part "R-EU_R0603"))
    )
    (comp (ref "R38")
      (value "10K")
      (footprint "eagle-import:R0603")
      (libsource (lib "eagle-import") (part "R-EU_R0603"))
    )
    (comp (ref "R39")
      (value "10K")
      (footprint "eagle-import:R0603")
      (libsource (lib "eagle-import") (part "R-EU_R0603"))
    )
    (comp (ref "R40")
      (value "10K")
      (footprint "eagle-import:R0603")
      (libsource (lib "eagle-import") (part "R-EU_R0603"))
    )
    (comp (ref "R41")
      (value "10K")
      (footprint "eagle-import:R0603")
      (libsource (lib "eagle-import") (part "R-EU_R0603"))
    )
    (comp (ref "R42")
      (value "10K")
      (footprint "eagle-import:R0603")
      (libsource (lib "eagle-import") (part "R-EU_R0603"))
    )
    (comp (ref "R43")
      (value "10K")
      (footprint "eagle-import:R0603")
      (libsource (lib "eagle-import") (part "R-EU_R0603"))
    )
    (comp (ref "R44")
      (value "10K")
      (footprint "eagle-import:R0603")
      (libsource (lib "eagle-import") (part "R-EU_R0603"))
    )
    (comp (ref "R45")
      (value "10K")
      (footprint "eagle-import:R0603")
      (libsource (lib "eagle-import") (part "R-EU_R0603"))
    )
    (comp (ref "R46")
      (value "10K")
      (footprint "eagle-import:R0603")
      (libsource (lib "eagle-import") (part "R-EU_R0603"))
    )
    (comp (ref "R47")
      (value "10K")
      (footprint "eagle-import:R0603")
      (libsource (lib "eagle-import") (part "R-EU_R0603"))
    )
    (comp (ref "R48")
      (value "10K")
      (footprint "eagle-import:R0603")
      (libsource (lib "eagle-import") (part "R-EU_R0603"))
    )
    (comp (ref "R49")
      (value "10K")
      (footprint "eagle-import:R0603")
      (libsource (lib "eagle-import") (part "R-EU_R0603"))
    )
    (comp (ref "U1")
      (value "2N7002")
      (footprint "eagle-import:TO-236AB_NEX")
      (fields
        (field (name "MANUFACTURER_PART_NUMBER") "2N7002,215")
        (field (name "COPYRIGHT") "Copyright (C) 2024 Ultra Librarian. All rights reserved.")
      )
      (libsource (lib "eagle-import") (part "2N7002"))
    )
  )
  (nets
    (net (code "1") (name "CS_MTX") (class "Default")
      (node (ref "KB_MATRIX") (pin "6") (pinfunction "6_6") (pintype "power_in"))
      (node (ref "M0") (pin "10") (pinfunction "OE/~{CS}_10") (pintype "bidirectional"))
      (node (ref "M1") (pin "10") (pinfunction "OE/~{CS}_10") (pintype "bidirectional"))
      (node (ref "M2") (pin "10") (pinfunction "OE/~{CS}_10") (pintype "bidirectional"))
      (node (ref "M3") (pin "10") (pinfunction "OE/~{CS}_10") (pintype "bidirectional"))
      (node (ref "M4") (pin "10") (pinfunction "OE/~{CS}_10") (pintype "bidirectional"))
      (node (ref "M5") (pin "10") (pinfunction "OE/~{CS}_10") (pintype "bidirectional"))
      (node (ref "U1") (pin "1") (pinfunction "1_1") (pintype "passive"))
    )
    (net (code "2") (name "GND") (class "Default")
      (node (ref "A1") (pin "3-GND") (pinfunction "3_GND_3-GND") (pintype "power_in"))
      (node (ref "A1.5") (pin "3-GND") (pinfunction "3_GND_3-GND") (pintype "power_in"))
      (node (ref "A10") (pin "3-GND") (pinfunction "3_GND_3-GND") (pintype "power_in"))
      (node (ref "A11") (pin "3-GND") (pinfunction "3_GND_3-GND") (pintype "power_in"))
      (node (ref "A12") (pin "3-GND") (pinfunction "3_GND_3-GND") (pintype "power_in"))
      (node (ref "A13") (pin "3-GND") (pinfunction "3_GND_3-GND") (pintype "power_in"))
      (node (ref "A14") (pin "3-GND") (pinfunction "3_GND_3-GND") (pintype "power_in"))
      (node (ref "A15") (pin "3-GND") (pinfunction "3_GND_3-GND") (pintype "power_in"))
      (node (ref "A16") (pin "3-GND") (pinfunction "3_GND_3-GND") (pintype "power_in"))
      (node (ref "A17") (pin "3-GND") (pinfunction "3_GND_3-GND") (pintype "power_in"))
      (node (ref "A18") (pin "3-GND") (pinfunction "3_GND_3-GND") (pintype "power_in"))
      (node (ref "A19") (pin "3-GND") (pinfunction "3_GND_3-GND") (pintype "power_in"))
      (node (ref "A2") (pin "3-GND") (pinfunction "3_GND_3-GND") (pintype "power_in"))
      (node (ref "A20") (pin "3-GND") (pinfunction "3_GND_3-GND") (pintype "power_in"))
      (node (ref "A21") (pin "3-GND") (pinfunction "3_GND_3-GND") (pintype "power_in"))
      (node (ref "A22") (pin "3-GND") (pinfunction "3_GND_3-GND") (pintype "power_in"))
      (node (ref "A23") (pin "3-GND") (pinfunction "3_GND_3-GND") (pintype "power_in"))
      (node (ref "A24") (pin "3-GND") (pinfunction "3_GND_3-GND") (pintype "power_in"))
      (node (ref "A25") (pin "3-GND") (pinfunction "3_GND_3-GND") (pintype "power_in"))
      (node (ref "A26") (pin "3-GND") (pinfunction "3_GND_3-GND") (pintype "power_in"))
      (node (ref "A27") (pin "3-GND") (pinfunction "3_GND_3-GND") (pintype "power_in"))
      (node (ref "A28") (pin "3-GND") (pinfunction "3_GND_3-GND") (pintype "power_in"))
      (node (ref "A29") (pin "3-GND") (pinfunction "3_GND_3-GND") (pintype "power_in"))
      (node (ref "A3") (pin "3-GND") (pinfunction "3_GND_3-GND") (pintype "power_in"))
      (node (ref "A30") (pin "3-GND") (pinfunction "3_GND_3-GND") (pintype "power_in"))
      (node (ref "A31") (pin "3-GND") (pinfunction "3_GND_3-GND") (pintype "power_in"))
      (node (ref "A32") (pin "3-GND") (pinfunction "3_GND_3-GND") (pintype "power_in"))
      (node (ref "A33") (pin "3-GND") (pinfunction "3_GND_3-GND") (pintype "power_in"))
      (node (ref "A34") (pin "3-GND") (pinfunction "3_GND_3-GND") (pintype "power_in"))
      (node (ref "A35") (pin "3-GND") (pinfunction "3_GND_3-GND") (pintype "power_in"))
      (node (ref "A36") (pin "3-GND") (pinfunction "3_GND_3-GND") (pintype "power_in"))
      (node (ref "A37") (pin "3-GND") (pinfunction "3_GND_3-GND") (pintype "power_in"))
      (node (ref "A38") (pin "3-GND") (pinfunction "3_GND_3-GND") (pintype "power_in"))
      (node (ref "A39") (pin "3-GND") (pinfunction "3_GND_3-GND") (pintype "power_in"))
      (node (ref "A4") (pin "3-GND") (pinfunction "3_GND_3-GND") (pintype "power_in"))
      (node (ref "A40") (pin "3-GND") (pinfunction "3_GND_3-GND") (pintype "power_in"))
      (node (ref "A41") (pin "3-GND") (pinfunction "3_GND_3-GND") (pintype "power_in"))
      (node (ref "A42") (pin "3-GND") (pinfunction "3_GND_3-GND") (pintype "power_in"))
      (node (ref "A43") (pin "3-GND") (pinfunction "3_GND_3-GND") (pintype "power_in"))
      (node (ref "A5") (pin "3-GND") (pinfunction "3_GND_3-GND") (pintype "power_in"))
      (node (ref "A6") (pin "3-GND") (pinfunction "3_GND_3-GND") (pintype "power_in"))
      (node (ref "A7") (pin "3-GND") (pinfunction "3_GND_3-GND") (pintype "power_in"))
      (node (ref "A8") (pin "3-GND") (pinfunction "3_GND_3-GND") (pintype "power_in"))
      (node (ref "A9") (pin "3-GND") (pinfunction "3_GND_3-GND") (pintype "power_in"))
      (node (ref "ARGB") (pin "1") (pinfunction "1_1") (pintype "power_in"))
      (node (ref "ARGB") (pin "NC1") (pinfunction "M_NC1") (pintype "bidirectional"))
      (node (ref "ARGB") (pin "NC2") (pinfunction "M_NC2") (pintype "bidirectional"))
      (node (ref "C1") (pin "2") (pinfunction "2_2") (pintype "passive"))
      (node (ref "C2") (pin "2") (pinfunction "2_2") (pintype "passive"))
      (node (ref "C3") (pin "2") (pinfunction "2_2") (pintype "passive"))
      (node (ref "C4") (pin "2") (pinfunction "2_2") (pintype "passive"))
      (node (ref "C5") (pin "2") (pinfunction "2_2") (pintype "passive"))
      (node (ref "C6") (pin "2") (pinfunction "2_2") (pintype "passive"))
      (node (ref "CA1") (pin "2") (pinfunction "2_2") (pintype "passive"))
      (node (ref "CA11") (pin "2") (pinfunction "2_2") (pintype "passive"))
      (node (ref "CA13") (pin "2") (pinfunction "2_2") (pintype "passive"))
      (node (ref "CA15") (pin "2") (pinfunction "2_2") (pintype "passive"))
      (node (ref "CA17") (pin "2") (pinfunction "2_2") (pintype "passive"))
      (node (ref "CA19") (pin "2") (pinfunction "2_2") (pintype "passive"))
      (node (ref "CA21") (pin "2") (pinfunction "2_2") (pintype "passive"))
      (node (ref "CA23") (pin "2") (pinfunction "2_2") (pintype "passive"))
      (node (ref "CA25") (pin "2") (pinfunction "2_2") (pintype "passive"))
      (node (ref "CA27") (pin "2") (pinfunction "2_2") (pintype "passive"))
      (node (ref "CA29") (pin "2") (pinfunction "2_2") (pintype "passive"))
      (node (ref "CA3") (pin "2") (pinfunction "2_2") (pintype "passive"))
      (node (ref "CA31") (pin "2") (pinfunction "2_2") (pintype "passive"))
      (node (ref "CA33") (pin "2") (pinfunction "2_2") (pintype "passive"))
      (node (ref "CA35") (pin "2") (pinfunction "2_2") (pintype "passive"))
      (node (ref "CA37") (pin "2") (pinfunction "2_2") (pintype "passive"))
      (node (ref "CA39") (pin "2") (pinfunction "2_2") (pintype "passive"))
      (node (ref "CA41") (pin "2") (pinfunction "2_2") (pintype "passive"))
      (node (ref "CA43") (pin "2") (pinfunction "2_2") (pintype "passive"))
      (node (ref "CA5") (pin "2") (pinfunction "2_2") (pintype "passive"))
      (node (ref "CA6") (pin "2") (pinfunction "2_2") (pintype "passive"))
      (node (ref "CA7") (pin "2") (pinfunction "2_2") (pintype "passive"))
      (node (ref "CA9") (pin "2") (pinfunction "2_2") (pintype "passive"))
      (node (ref "I44") (pin "G") (pinfunction "G_G") (pintype "power_in"))
      (node (ref "KB_MATRIX") (pin "1") (pinfunction "1_1") (pintype "power_in"))
      (node (ref "KB_MATRIX") (pin "NC1") (pinfunction "M_NC1") (pintype "bidirectional"))
      (node (ref "KB_MATRIX") (pin "NC2") (pinfunction "M_NC2") (pintype "bidirectional"))
      (node (ref "M0") (pin "8") (pinfunction "GND_8") (pintype "bidirectional"))
      (node (ref "M1") (pin "8") (pinfunction "GND_8") (pintype "bidirectional"))
      (node (ref "M2") (pin "8") (pinfunction "GND_8") (pintype "bidirectional"))
      (node (ref "M3") (pin "8") (pinfunction "GND_8") (pintype "bidirectional"))
      (node (ref "M4") (pin "8") (pinfunction "GND_8") (pintype "bidirectional"))
      (node (ref "M5") (pin "14") (pinfunction "SA_14") (pintype "bidirectional"))
      (node (ref "M5") (pin "8") (pinfunction "GND_8") (pintype "bidirectional"))
      (node (ref "R10") (pin "1") (pinfunction "1_1") (pintype "passive"))
      (node (ref "R11") (pin "1") (pinfunction "1_1") (pintype "passive"))
      (node (ref "R12") (pin "1") (pinfunction "1_1") (pintype "passive"))
      (node (ref "R13") (pin "1") (pinfunction "1_1") (pintype "passive"))
      (node (ref "R14") (pin "2") (pinfunction "2_2") (pintype "passive"))
      (node (ref "R15") (pin "2") (pinfunction "2_2") (pintype "passive"))
      (node (ref "R16") (pin "2") (pinfunction "2_2") (pintype "passive"))
      (node (ref "R17") (pin "2") (pinfunction "2_2") (pintype "passive"))
      (node (ref "R18") (pin "1") (pinfunction "1_1") (pintype "passive"))
      (node (ref "R19") (pin "1") (pinfunction "1_1") (pintype "passive"))
      (node (ref "R2") (pin "1") (pinfunction "1_1") (pintype "passive"))
      (node (ref "R20") (pin "1") (pinfunction "1_1") (pintype "passive"))
      (node (ref "R21") (pin "1") (pinfunction "1_1") (pintype "passive"))
      (node (ref "R22") (pin "2") (pinfunction "2_2") (pintype "passive"))
      (node (ref "R23") (pin "2") (pinfunction "2_2") (pintype "passive"))
      (node (ref "R24") (pin "2") (pinfunction "2_2") (pintype "passive"))
      (node (ref "R25") (pin "2") (pinfunction "2_2") (pintype "passive"))
      (node (ref "R26") (pin "1") (pinfunction "1_1") (pintype "passive"))
      (node (ref "R27") (pin "1") (pinfunction "1_1") (pintype "passive"))
      (node (ref "R28") (pin "1") (pinfunction "1_1") (pintype "passive"))
      (node (ref "R29") (pin "1") (pinfunction "1_1") (pintype "passive"))
      (node (ref "R3") (pin "1") (pinfunction "1_1") (pintype "passive"))
      (node (ref "R30") (pin "2") (pinfunction "2_2") (pintype "passive"))
      (node (ref "R31") (pin "2") (pinfunction "2_2") (pintype "passive"))
      (node (ref "R32") (pin "2") (pinfunction "2_2") (pintype "passive"))
      (node (ref "R33") (pin "2") (pinfunction "2_2") (pintype "passive"))
      (node (ref "R34") (pin "1") (pinfunction "1_1") (pintype "passive"))
      (node (ref "R35") (pin "1") (pinfunction "1_1") (pintype "passive"))
      (node (ref "R36") (pin "1") (pinfunction "1_1") (pintype "passive"))
      (node (ref "R37") (pin "1") (pinfunction "1_1") (pintype "passive"))
      (node (ref "R38") (pin "2") (pinfunction "2_2") (pintype "passive"))
      (node (ref "R39") (pin "2") (pinfunction "2_2") (pintype "passive"))
      (node (ref "R4") (pin "1") (pinfunction "1_1") (pintype "passive"))
      (node (ref "R40") (pin "2") (pinfunction "2_2") (pintype "passive"))
      (node (ref "R41") (pin "2") (pinfunction "2_2") (pintype "passive"))
      (node (ref "R42") (pin "1") (pinfunction "1_1") (pintype "passive"))
      (node (ref "R43") (pin "1") (pinfunction "1_1") (pintype "passive"))
      (node (ref "R44") (pin "1") (pinfunction "1_1") (pintype "passive"))
      (node (ref "R45") (pin "1") (pinfunction "1_1") (pintype "passive"))
      (node (ref "R46") (pin "2") (pinfunction "2_2") (pintype "passive"))
      (node (ref "R47") (pin "2") (pinfunction "2_2") (pintype "passive"))
      (node (ref "R48") (pin "2") (pinfunction "2_2") (pintype "passive"))
      (node (ref "R49") (pin "2") (pinfunction "2_2") (pintype "passive"))
      (node (ref "R5") (pin "1") (pinfunction "1_1") (pintype "passive"))
      (node (ref "R6") (pin "2") (pinfunction "2_2") (pintype "passive"))
      (node (ref "R7") (pin "2") (pinfunction "2_2") (pintype "passive"))
      (node (ref "R8") (pin "2") (pinfunction "2_2") (pintype "passive"))
      (node (ref "R9") (pin "2") (pinfunction "2_2") (pintype "passive"))
      (node (ref "U1") (pin "2") (pinfunction "3_2") (pintype "passive"))
    )
    (net (code "3") (name "K00") (class "Default")
      (node (ref "M0") (pin "15") (pinfunction "A_15") (pintype "bidirectional"))
      (node (ref "R2") (pin "2") (pinfunction "2_2") (pintype "passive"))
      (node (ref "SW_ESC") (pin "1@1") (pinfunction "P_1@1") (pintype "passive"))
      (node (ref "SW_ESC") (pin "1@2") (pinfunction "P_1@2") (pintype "passive"))
    )
    (net (code "4") (name "K01") (class "Default")
      (node (ref "M0") (pin "1") (pinfunction "B_1") (pintype "bidirectional"))
      (node (ref "R3") (pin "2") (pinfunction "2_2") (pintype "passive"))
      (node (ref "SW_Q") (pin "1@1") (pinfunction "P_1@1") (pintype "passive"))
      (node (ref "SW_Q") (pin "1@2") (pinfunction "P_1@2") (pintype "passive"))
    )
    (net (code "5") (name "K02") (class "Default")
      (node (ref "M0") (pin "2") (pinfunction "C_2") (pintype "bidirectional"))
      (node (ref "R4") (pin "2") (pinfunction "2_2") (pintype "passive"))
      (node (ref "SW_W") (pin "1@1") (pinfunction "P_1@1") (pintype "passive"))
      (node (ref "SW_W") (pin "1@2") (pinfunction "P_1@2") (pintype "passive"))
    )
    (net (code "6") (name "K03") (class "Default")
      (node (ref "M0") (pin "3") (pinfunction "D_3") (pintype "bidirectional"))
      (node (ref "R5") (pin "2") (pinfunction "2_2") (pintype "passive"))
      (node (ref "SW_E") (pin "1@1") (pinfunction "P_1@1") (pintype "passive"))
      (node (ref "SW_E") (pin "1@2") (pinfunction "P_1@2") (pintype "passive"))
    )
    (net (code "7") (name "K04") (class "Default")
      (node (ref "M0") (pin "4") (pinfunction "E_4") (pintype "bidirectional"))
      (node (ref "R6") (pin "1") (pinfunction "1_1") (pintype "passive"))
      (node (ref "SW_TAB") (pin "1@1") (pinfunction "P_1@1") (pintype "passive"))
      (node (ref "SW_TAB") (pin "1@2") (pinfunction "P_1@2") (pintype "passive"))
    )
    (net (code "8") (name "K05") (class "Default")
      (node (ref "M0") (pin "5") (pinfunction "F_5") (pintype "bidirectional"))
      (node (ref "R7") (pin "1") (pinfunction "1_1") (pintype "passive"))
      (node (ref "SW_A") (pin "1@1") (pinfunction "P_1@1") (pintype "passive"))
      (node (ref "SW_A") (pin "1@2") (pinfunction "P_1@2") (pintype "passive"))
    )
    (net (code "9") (name "K06") (class "Default")
      (node (ref "M0") (pin "6") (pinfunction "G_6") (pintype "bidirectional"))
      (node (ref "R8") (pin "1") (pinfunction "1_1") (pintype "passive"))
      (node (ref "SW_S") (pin "1@1") (pinfunction "P_1@1") (pintype "passive"))
      (node (ref "SW_S") (pin "1@2") (pinfunction "P_1@2") (pintype "passive"))
    )
    (net (code "10") (name "K07") (class "Default")
      (node (ref "M0") (pin "7") (pinfunction "H_7") (pintype "bidirectional"))
      (node (ref "R9") (pin "1") (pinfunction "1_1") (pintype "passive"))
      (node (ref "SW_D") (pin "1@1") (pinfunction "P_1@1") (pintype "passive"))
      (node (ref "SW_D") (pin "1@2") (pinfunction "P_1@2") (pintype "passive"))
    )
    (net (code "11") (name "K10") (class "Default")
      (node (ref "M1") (pin "15") (pinfunction "A_15") (pintype "bidirectional"))
      (node (ref "R10") (pin "2") (pinfunction "2_2") (pintype "passive"))
      (node (ref "SW_R") (pin "1@1") (pinfunction "P_1@1") (pintype "passive"))
      (node (ref "SW_R") (pin "1@2") (pinfunction "P_1@2") (pintype "passive"))
    )
    (net (code "12") (name "K11") (class "Default")
      (node (ref "M1") (pin "1") (pinfunction "B_1") (pintype "bidirectional"))
      (node (ref "R11") (pin "2") (pinfunction "2_2") (pintype "passive"))
      (node (ref "SW_T") (pin "1@1") (pinfunction "P_1@1") (pintype "passive"))
      (node (ref "SW_T") (pin "1@2") (pinfunction "P_1@2") (pintype "passive"))
    )
    (net (code "13") (name "K12") (class "Default")
      (node (ref "M1") (pin "2") (pinfunction "C_2") (pintype "bidirectional"))
      (node (ref "R12") (pin "2") (pinfunction "2_2") (pintype "passive"))
      (node (ref "SW_Y") (pin "1@1") (pinfunction "P_1@1") (pintype "passive"))
      (node (ref "SW_Y") (pin "1@2") (pinfunction "P_1@2") (pintype "passive"))
    )
    (net (code "14") (name "K13") (class "Default")
      (node (ref "M1") (pin "3") (pinfunction "D_3") (pintype "bidirectional"))
      (node (ref "R13") (pin "2") (pinfunction "2_2") (pintype "passive"))
      (node (ref "SW_U") (pin "1@1") (pinfunction "P_1@1") (pintype "passive"))
      (node (ref "SW_U") (pin "1@2") (pinfunction "P_1@2") (pintype "passive"))
    )
    (net (code "15") (name "K14") (class "Default")
      (node (ref "M1") (pin "4") (pinfunction "E_4") (pintype "bidirectional"))
      (node (ref "R14") (pin "1") (pinfunction "1_1") (pintype "passive"))
      (node (ref "SW_F") (pin "1@1") (pinfunction "P_1@1") (pintype "passive"))
      (node (ref "SW_F") (pin "1@2") (pinfunction "P_1@2") (pintype "passive"))
    )
    (net (code "16") (name "K15") (class "Default")
      (node (ref "M1") (pin "5") (pinfunction "F_5") (pintype "bidirectional"))
      (node (ref "R15") (pin "1") (pinfunction "1_1") (pintype "passive"))
      (node (ref "SW_G") (pin "1@1") (pinfunction "P_1@1") (pintype "passive"))
      (node (ref "SW_G") (pin "1@2") (pinfunction "P_1@2") (pintype "passive"))
    )
    (net (code "17") (name "K16") (class "Default")
      (node (ref "M1") (pin "6") (pinfunction "G_6") (pintype "bidirectional"))
      (node (ref "R16") (pin "1") (pinfunction "1_1") (pintype "passive"))
      (node (ref "SW_H") (pin "1@1") (pinfunction "P_1@1") (pintype "passive"))
      (node (ref "SW_H") (pin "1@2") (pinfunction "P_1@2") (pintype "passive"))
    )
    (net (code "18") (name "K17") (class "Default")
      (node (ref "M1") (pin "7") (pinfunction "H_7") (pintype "bidirectional"))
      (node (ref "R17") (pin "1") (pinfunction "1_1") (pintype "passive"))
      (node (ref "SW_J") (pin "1@1") (pinfunction "P_1@1") (pintype "passive"))
      (node (ref "SW_J") (pin "1@2") (pinfunction "P_1@2") (pintype "passive"))
    )
    (net (code "19") (name "K20") (class "Default")
      (node (ref "M2") (pin "15") (pinfunction "A_15") (pintype "bidirectional"))
      (node (ref "R18") (pin "2") (pinfunction "2_2") (pintype "passive"))
      (node (ref "SW_I") (pin "1@1") (pinfunction "P_1@1") (pintype "passive"))
      (node (ref "SW_I") (pin "1@2") (pinfunction "P_1@2") (pintype "passive"))
    )
    (net (code "20") (name "K21") (class "Default")
      (node (ref "M2") (pin "1") (pinfunction "B_1") (pintype "bidirectional"))
      (node (ref "R19") (pin "2") (pinfunction "2_2") (pintype "passive"))
      (node (ref "SW_O") (pin "1@1") (pinfunction "P_1@1") (pintype "passive"))
      (node (ref "SW_O") (pin "1@2") (pinfunction "P_1@2") (pintype "passive"))
    )
    (net (code "21") (name "K22") (class "Default")
      (node (ref "M2") (pin "2") (pinfunction "C_2") (pintype "bidirectional"))
      (node (ref "R20") (pin "2") (pinfunction "2_2") (pintype "passive"))
      (node (ref "SW_P") (pin "1@1") (pinfunction "P_1@1") (pintype "passive"))
      (node (ref "SW_P") (pin "1@2") (pinfunction "P_1@2") (pintype "passive"))
    )
    (net (code "22") (name "K23") (class "Default")
      (node (ref "M2") (pin "3") (pinfunction "D_3") (pintype "bidirectional"))
      (node (ref "R21") (pin "2") (pinfunction "2_2") (pintype "passive"))
      (node (ref "SW_BSP") (pin "1@1") (pinfunction "P_1@1") (pintype "passive"))
      (node (ref "SW_BSP") (pin "1@2") (pinfunction "P_1@2") (pintype "passive"))
    )
    (net (code "23") (name "K24") (class "Default")
      (node (ref "M2") (pin "4") (pinfunction "E_4") (pintype "bidirectional"))
      (node (ref "R22") (pin "1") (pinfunction "1_1") (pintype "passive"))
      (node (ref "SW_K") (pin "1@1") (pinfunction "P_1@1") (pintype "passive"))
      (node (ref "SW_K") (pin "1@2") (pinfunction "P_1@2") (pintype "passive"))
    )
    (net (code "24") (name "K25") (class "Default")
      (node (ref "M2") (pin "5") (pinfunction "F_5") (pintype "bidirectional"))
      (node (ref "R23") (pin "1") (pinfunction "1_1") (pintype "passive"))
      (node (ref "SW_L") (pin "1@1") (pinfunction "P_1@1") (pintype "passive"))
      (node (ref "SW_L") (pin "1@2") (pinfunction "P_1@2") (pintype "passive"))
    )
    (net (code "25") (name "K26") (class "Default")
      (node (ref "M2") (pin "6") (pinfunction "G_6") (pintype "bidirectional"))
      (node (ref "R24") (pin "1") (pinfunction "1_1") (pintype "passive"))
      (node (ref "SW_ENT") (pin "1@1") (pinfunction "P_1@1") (pintype "passive"))
      (node (ref "SW_ENT") (pin "1@2") (pinfunction "P_1@2") (pintype "passive"))
    )
    (net (code "26") (name "K30") (class "Default")
      (node (ref "M3") (pin "15") (pinfunction "A_15") (pintype "bidirectional"))
      (node (ref "R26") (pin "2") (pinfunction "2_2") (pintype "passive"))
      (node (ref "SW_LS") (pin "1@1") (pinfunction "P_1@1") (pintype "passive"))
      (node (ref "SW_LS") (pin "1@2") (pinfunction "P_1@2") (pintype "passive"))
    )
    (net (code "27") (name "K31") (class "Default")
      (node (ref "M3") (pin "1") (pinfunction "B_1") (pintype "bidirectional"))
      (node (ref "R27") (pin "2") (pinfunction "2_2") (pintype "passive"))
      (node (ref "SW_Z") (pin "1@1") (pinfunction "P_1@1") (pintype "passive"))
      (node (ref "SW_Z") (pin "1@2") (pinfunction "P_1@2") (pintype "passive"))
    )
    (net (code "28") (name "K32") (class "Default")
      (node (ref "M3") (pin "2") (pinfunction "C_2") (pintype "bidirectional"))
      (node (ref "R28") (pin "2") (pinfunction "2_2") (pintype "passive"))
      (node (ref "SW_X") (pin "1@1") (pinfunction "P_1@1") (pintype "passive"))
      (node (ref "SW_X") (pin "1@2") (pinfunction "P_1@2") (pintype "passive"))
    )
    (net (code "29") (name "K34") (class "Default")
      (node (ref "M3") (pin "4") (pinfunction "E_4") (pintype "bidirectional"))
      (node (ref "R30") (pin "1") (pinfunction "1_1") (pintype "passive"))
      (node (ref "SW_LC") (pin "1@1") (pinfunction "P_1@1") (pintype "passive"))
      (node (ref "SW_LC") (pin "1@2") (pinfunction "P_1@2") (pintype "passive"))
    )
    (net (code "30") (name "K35") (class "Default")
      (node (ref "M3") (pin "5") (pinfunction "F_5") (pintype "bidirectional"))
      (node (ref "R31") (pin "1") (pinfunction "1_1") (pintype "passive"))
      (node (ref "SW_LW") (pin "1@1") (pinfunction "P_1@1") (pintype "passive"))
      (node (ref "SW_LW") (pin "1@2") (pinfunction "P_1@2") (pintype "passive"))
    )
    (net (code "31") (name "K36") (class "Default")
      (node (ref "M3") (pin "6") (pinfunction "G_6") (pintype "bidirectional"))
      (node (ref "R32") (pin "1") (pinfunction "1_1") (pintype "passive"))
      (node (ref "SW_LA") (pin "1@1") (pinfunction "P_1@1") (pintype "passive"))
      (node (ref "SW_LA") (pin "1@2") (pinfunction "P_1@2") (pintype "passive"))
    )
    (net (code "32") (name "K40") (class "Default")
      (node (ref "M4") (pin "15") (pinfunction "A_15") (pintype "bidirectional"))
      (node (ref "R34") (pin "2") (pinfunction "2_2") (pintype "passive"))
      (node (ref "SW_C") (pin "1@1") (pinfunction "P_1@1") (pintype "passive"))
      (node (ref "SW_C") (pin "1@2") (pinfunction "P_1@2") (pintype "passive"))
    )
    (net (code "33") (name "K41") (class "Default")
      (node (ref "M4") (pin "1") (pinfunction "B_1") (pintype "bidirectional"))
      (node (ref "R35") (pin "2") (pinfunction "2_2") (pintype "passive"))
      (node (ref "SW_V") (pin "1@1") (pinfunction "P_1@1") (pintype "passive"))
      (node (ref "SW_V") (pin "1@2") (pinfunction "P_1@2") (pintype "passive"))
    )
    (net (code "34") (name "K42") (class "Default")
      (node (ref "M4") (pin "2") (pinfunction "C_2") (pintype "bidirectional"))
      (node (ref "R36") (pin "2") (pinfunction "2_2") (pintype "passive"))
      (node (ref "SW_B") (pin "1@1") (pinfunction "P_1@1") (pintype "passive"))
      (node (ref "SW_B") (pin "1@2") (pinfunction "P_1@2") (pintype "passive"))
    )
    (net (code "35") (name "K43") (class "Default")
      (node (ref "M4") (pin "3") (pinfunction "D_3") (pintype "bidirectional"))
      (node (ref "R37") (pin "2") (pinfunction "2_2") (pintype "passive"))
      (node (ref "SW_N") (pin "1@1") (pinfunction "P_1@1") (pintype "passive"))
      (node (ref "SW_N") (pin "1@2") (pinfunction "P_1@2") (pintype "passive"))
    )
    (net (code "36") (name "K44") (class "Default")
      (node (ref "M4") (pin "4") (pinfunction "E_4") (pintype "bidirectional"))
      (node (ref "R38") (pin "1") (pinfunction "1_1") (pintype "passive"))
      (node (ref "SW_SPC_1") (pin "1@1") (pinfunction "P_1@1") (pintype "passive"))
      (node (ref "SW_SPC_1") (pin "1@2") (pinfunction "P_1@2") (pintype "passive"))
    )
    (net (code "37") (name "K45") (class "Default")
      (node (ref "M4") (pin "5") (pinfunction "F_5") (pintype "bidirectional"))
      (node (ref "R39") (pin "1") (pinfunction "1_1") (pintype "passive"))
      (node (ref "SW_SPC_2") (pin "1@1") (pinfunction "P_1@1") (pintype "passive"))
      (node (ref "SW_SPC_2") (pin "1@2") (pinfunction "P_1@2") (pintype "passive"))
    )
    (net (code "38") (name "K50") (class "Default")
      (node (ref "M5") (pin "15") (pinfunction "A_15") (pintype "bidirectional"))
      (node (ref "R42") (pin "2") (pinfunction "2_2") (pintype "passive"))
      (node (ref "SW_M") (pin "1@1") (pinfunction "P_1@1") (pintype "passive"))
      (node (ref "SW_M") (pin "1@2") (pinfunction "P_1@2") (pintype "passive"))
    )
    (net (code "39") (name "K51") (class "Default")
      (node (ref "M5") (pin "1") (pinfunction "B_1") (pintype "bidirectional"))
      (node (ref "R43") (pin "2") (pinfunction "2_2") (pintype "passive"))
      (node (ref "SW_RS") (pin "1@1") (pinfunction "P_1@1") (pintype "passive"))
      (node (ref "SW_RS") (pin "1@2") (pinfunction "P_1@2") (pintype "passive"))
    )
    (net (code "40") (name "K52") (class "Default")
      (node (ref "M5") (pin "2") (pinfunction "C_2") (pintype "bidirectional"))
      (node (ref "R44") (pin "2") (pinfunction "2_2") (pintype "passive"))
      (node (ref "SW_UP") (pin "1@1") (pinfunction "P_1@1") (pintype "passive"))
      (node (ref "SW_UP") (pin "1@2") (pinfunction "P_1@2") (pintype "passive"))
    )
    (net (code "41") (name "K53") (class "Default")
      (node (ref "M5") (pin "3") (pinfunction "D_3") (pintype "bidirectional"))
      (node (ref "R45") (pin "2") (pinfunction "2_2") (pintype "passive"))
      (node (ref "SW_DEL") (pin "1@1") (pinfunction "P_1@1") (pintype "passive"))
      (node (ref "SW_DEL") (pin "1@2") (pinfunction "P_1@2") (pintype "passive"))
    )
    (net (code "42") (name "K54") (class "Default")
      (node (ref "M5") (pin "4") (pinfunction "E_4") (pintype "bidirectional"))
      (node (ref "R46") (pin "1") (pinfunction "1_1") (pintype "passive"))
      (node (ref "SW_LF") (pin "1@1") (pinfunction "P_1@1") (pintype "passive"))
      (node (ref "SW_LF") (pin "1@2") (pinfunction "P_1@2") (pintype "passive"))
    )
    (net (code "43") (name "K55") (class "Default")
      (node (ref "M5") (pin "5") (pinfunction "F_5") (pintype "bidirectional"))
      (node (ref "R47") (pin "1") (pinfunction "1_1") (pintype "passive"))
      (node (ref "SW_DN") (pin "1@1") (pinfunction "P_1@1") (pintype "passive"))
      (node (ref "SW_DN") (pin "1@2") (pinfunction "P_1@2") (pintype "passive"))
    )
    (net (code "44") (name "K56") (class "Default")
      (node (ref "M5") (pin "6") (pinfunction "G_6") (pintype "bidirectional"))
      (node (ref "R48") (pin "1") (pinfunction "1_1") (pintype "passive"))
      (node (ref "SW_RT") (pin "1@1") (pinfunction "P_1@1") (pintype "passive"))
      (node (ref "SW_RT") (pin "1@2") (pinfunction "P_1@2") (pintype "passive"))
    )
    (net (code "45") (name "LATCH_MTX") (class "Default")
      (node (ref "M0") (pin "12") (pinfunction "LATCH_12") (pintype "bidirectional"))
      (node (ref "M0") (pin "13") (pinfunction "SS/~{PL}_13") (pintype "bidirectional"))
      (node (ref "M1") (pin "12") (pinfunction "LATCH_12") (pintype "bidirectional"))
      (node (ref "M1") (pin "13") (pinfunction "SS/~{PL}_13") (pintype "bidirectional"))
      (node (ref "M2") (pin "12") (pinfunction "LATCH_12") (pintype "bidirectional"))
      (node (ref "M2") (pin "13") (pinfunction "SS/~{PL}_13") (pintype "bidirectional"))
      (node (ref "M3") (pin "12") (pinfunction "LATCH_12") (pintype "bidirectional"))
      (node (ref "M3") (pin "13") (pinfunction "SS/~{PL}_13") (pintype "bidirectional"))
      (node (ref "M4") (pin "12") (pinfunction "LATCH_12") (pintype "bidirectional"))
      (node (ref "M4") (pin "13") (pinfunction "SS/~{PL}_13") (pintype "bidirectional"))
      (node (ref "M5") (pin "12") (pinfunction "LATCH_12") (pintype "bidirectional"))
      (node (ref "M5") (pin "13") (pinfunction "SS/~{PL}_13") (pintype "bidirectional"))
      (node (ref "R1") (pin "1") (pinfunction "1_1") (pintype "passive"))
      (node (ref "U1") (pin "3") (pinfunction "2_3") (pintype "passive"))
    )
    (net (code "46") (name "MATRIX_0_1") (class "Default")
      (node (ref "M0") (pin "14") (pinfunction "SA_14") (pintype "bidirectional"))
      (node (ref "M1") (pin "9") (pinfunction "QH_9") (pintype "bidirectional"))
    )
    (net (code "47") (name "MATRIX_1_2") (class "Default")
      (node (ref "M1") (pin "14") (pinfunction "SA_14") (pintype "bidirectional"))
      (node (ref "M2") (pin "9") (pinfunction "QH_9") (pintype "bidirectional"))
    )
    (net (code "48") (name "MATRIX_2_3") (class "Default")
      (node (ref "M2") (pin "14") (pinfunction "SA_14") (pintype "bidirectional"))
      (node (ref "M3") (pin "9") (pinfunction "QH_9") (pintype "bidirectional"))
    )
    (net (code "49") (name "MATRIX_3_4") (class "Default")
      (node (ref "M3") (pin "14") (pinfunction "SA_14") (pintype "bidirectional"))
      (node (ref "M4") (pin "9") (pinfunction "QH_9") (pintype "bidirectional"))
    )
    (net (code "50") (name "MATRIX_4_5") (class "Default")
      (node (ref "M4") (pin "14") (pinfunction "SA_14") (pintype "bidirectional"))
      (node (ref "M5") (pin "9") (pinfunction "QH_9") (pintype "bidirectional"))
    )
    (net (code "51") (name "MISO") (class "Default")
      (node (ref "KB_MATRIX") (pin "4") (pinfunction "4_4") (pintype "power_in"))
      (node (ref "M0") (pin "9") (pinfunction "QH_9") (pintype "bidirectional"))
    )
    (net (code "52") (name "MOSI") (class "Default")
      (node (ref "KB_MATRIX") (pin "3") (pinfunction "3_3") (pintype "passive"))
    )
    (net (code "53") (name "Net-(A1-2_DOUT)") (class "Default")
      (node (ref "A1") (pin "2-DOUT") (pinfunction "2_DOUT_2-DOUT") (pintype "output"))
      (node (ref "A1.5") (pin "4-DIN") (pinfunction "4_DIN_4-DIN") (pintype "input"))
    )
    (net (code "54") (name "Net-(A1-4_DIN)") (class "Default")
      (node (ref "A1") (pin "4-DIN") (pinfunction "4_DIN_4-DIN") (pintype "input"))
      (node (ref "ARGB") (pin "3") (pinfunction "3_3") (pintype "passive"))
    )
    (net (code "55") (name "Net-(A1.5-2_DOUT)") (class "Default")
      (node (ref "A1.5") (pin "2-DOUT") (pinfunction "2_DOUT_2-DOUT") (pintype "output"))
      (node (ref "A2") (pin "4-DIN") (pinfunction "4_DIN_4-DIN") (pintype "input"))
    )
    (net (code "56") (name "Net-(A2-2_DOUT)") (class "Default")
      (node (ref "A2") (pin "2-DOUT") (pinfunction "2_DOUT_2-DOUT") (pintype "output"))
      (node (ref "A3") (pin "4-DIN") (pinfunction "4_DIN_4-DIN") (pintype "input"))
    )
    (net (code "57") (name "Net-(A3-2_DOUT)") (class "Default")
      (node (ref "A3") (pin "2-DOUT") (pinfunction "2_DOUT_2-DOUT") (pintype "output"))
      (node (ref "A4") (pin "4-DIN") (pinfunction "4_DIN_4-DIN") (pintype "input"))
    )
    (net (code "58") (name "Net-(A4-2_DOUT)") (class "Default")
      (node (ref "A4") (pin "2-DOUT") (pinfunction "2_DOUT_2-DOUT") (pintype "output"))
      (node (ref "A5") (pin "4-DIN") (pinfunction "4_DIN_4-DIN") (pintype "input"))
    )
    (net (code "59") (name "Net-(A5-2_DOUT)") (class "Default")
      (node (ref "A5") (pin "2-DOUT") (pinfunction "2_DOUT_2-DOUT") (pintype "output"))
      (node (ref "A6") (pin "4-DIN") (pinfunction "4_DIN_4-DIN") (pintype "input"))
    )
    (net (code "60") (name "Net-(A6-2_DOUT)") (class "Default")
      (node (ref "A6") (pin "2-DOUT") (pinfunction "2_DOUT_2-DOUT") (pintype "output"))
      (node (ref "A7") (pin "4-DIN") (pinfunction "4_DIN_4-DIN") (pintype "input"))
    )
    (net (code "61") (name "Net-(A7-2_DOUT)") (class "Default")
      (node (ref "A7") (pin "2-DOUT") (pinfunction "2_DOUT_2-DOUT") (pintype "output"))
      (node (ref "A8") (pin "4-DIN") (pinfunction "4_DIN_4-DIN") (pintype "input"))
    )
    (net (code "62") (name "Net-(A8-2_DOUT)") (class "Default")
      (node (ref "A8") (pin "2-DOUT") (pinfunction "2_DOUT_2-DOUT") (pintype "output"))
      (node (ref "A9") (pin "4-DIN") (pinfunction "4_DIN_4-DIN") (pintype "input"))
    )
    (net (code "63") (name "Net-(A10-2_DOUT)") (class "Default")
      (node (ref "A10") (pin "2-DOUT") (pinfunction "2_DOUT_2-DOUT") (pintype "output"))
      (node (ref "A11") (pin "4-DIN") (pinfunction "4_DIN_4-DIN") (pintype "input"))
    )
    (net (code "64") (name "Net-(A10-4_DIN)") (class "Default")
      (node (ref "A10") (pin "4-DIN") (pinfunction "4_DIN_4-DIN") (pintype "input"))
      (node (ref "A9") (pin "2-DOUT") (pinfunction "2_DOUT_2-DOUT") (pintype "output"))
    )
    (net (code "65") (name "Net-(A11-2_DOUT)") (class "Default")
      (node (ref "A11") (pin "2-DOUT") (pinfunction "2_DOUT_2-DOUT") (pintype "output"))
      (node (ref "A12") (pin "4-DIN") (pinfunction "4_DIN_4-DIN") (pintype "input"))
    )
    (net (code "66") (name "Net-(A12-2_DOUT)") (class "Default")
      (node (ref "A12") (pin "2-DOUT") (pinfunction "2_DOUT_2-DOUT") (pintype "output"))
      (node (ref "A13") (pin "4-DIN") (pinfunction "4_DIN_4-DIN") (pintype "input"))
    )
    (net (code "67") (name "Net-(A13-2_DOUT)") (class "Default")
      (node (ref "A13") (pin "2-DOUT") (pinfunction "2_DOUT_2-DOUT") (pintype "output"))
      (node (ref "A14") (pin "4-DIN") (pinfunction "4_DIN_4-DIN") (pintype "input"))
    )
    (net (code "68") (name "Net-(A14-2_DOUT)") (class "Default")
      (node (ref "A14") (pin "2-DOUT") (pinfunction "2_DOUT_2-DOUT") (pintype "output"))
      (node (ref "A15") (pin "4-DIN") (pinfunction "4_DIN_4-DIN") (pintype "input"))
    )
    (net (code "69") (name "Net-(A15-2_DOUT)") (class "Default")
      (node (ref "A15") (pin "2-DOUT") (pinfunction "2_DOUT_2-DOUT") (pintype "output"))
      (node (ref "A16") (pin "4-DIN") (pinfunction "4_DIN_4-DIN") (pintype "input"))
    )
    (net (code "70") (name "Net-(A16-2_DOUT)") (class "Default")
      (node (ref "A16") (pin "2-DOUT") (pinfunction "2_DOUT_2-DOUT") (pintype "output"))
      (node (ref "A17") (pin "4-DIN") (pinfunction "4_DIN_4-DIN") (pintype "input"))
    )
    (net (code "71") (name "Net-(A17-2_DOUT)") (class "Default")
      (node (ref "A17") (pin "2-DOUT") (pinfunction "2_DOUT_2-DOUT") (pintype "output"))
      (node (ref "A18") (pin "4-DIN") (pinfunction "4_DIN_4-DIN") (pintype "input"))
    )
    (net (code "72") (name "Net-(A18-2_DOUT)") (class "Default")
      (node (ref "A18") (pin "2-DOUT") (pinfunction "2_DOUT_2-DOUT") (pintype "output"))
      (node (ref "A19") (pin "4-DIN") (pinfunction "4_DIN_4-DIN") (pintype "input"))
    )
    (net (code "73") (name "Net-(A19-2_DOUT)") (class "Default")
      (node (ref "A19") (pin "2-DOUT") (pinfunction "2_DOUT_2-DOUT") (pintype "output"))
      (node (ref "A20") (pin "4-DIN") (pinfunction "4_DIN_4-DIN") (pintype "input"))
    )
    (net (code "74") (name "Net-(A20-2_DOUT)") (class "Default")
      (node (ref "A20") (pin "2-DOUT") (pinfunction "2_DOUT_2-DOUT") (pintype "output"))
      (node (ref "A21") (pin "4-DIN") (pinfunction "4_DIN_4-DIN") (pintype "input"))
    )
    (net (code "75") (name "Net-(A21-2_DOUT)") (class "Default")
      (node (ref "A21") (pin "2-DOUT") (pinfunction "2_DOUT_2-DOUT") (pintype "output"))
      (node (ref "A22") (pin "4-DIN") (pinfunction "4_DIN_4-DIN") (pintype "input"))
    )
    (net (code "76") (name "Net-(A22-2_DOUT)") (class "Default")
      (node (ref "A22") (pin "2-DOUT") (pinfunction "2_DOUT_2-DOUT") (pintype "output"))
      (node (ref "A23") (pin "4-DIN") (pinfunction "4_DIN_4-DIN") (pintype "input"))
    )
    (net (code "77") (name "Net-(A23-2_DOUT)") (class "Default")
      (node (ref "A23") (pin "2-DOUT") (pinfunction "2_DOUT_2-DOUT") (pintype "output"))
      (node (ref "A24") (pin "4-DIN") (pinfunction "4_DIN_4-DIN") (pintype "input"))
    )
    (net (code "78") (name "Net-(A24-2_DOUT)") (class "Default")
      (node (ref "A24") (pin "2-DOUT") (pinfunction "2_DOUT_2-DOUT") (pintype "output"))
      (node (ref "A25") (pin "4-DIN") (pinfunction "4_DIN_4-DIN") (pintype "input"))
    )
    (net (code "79") (name "Net-(A25-2_DOUT)") (class "Default")
      (node (ref "A25") (pin "2-DOUT") (pinfunction "2_DOUT_2-DOUT") (pintype "output"))
      (node (ref "A26") (pin "4-DIN") (pinfunction "4_DIN_4-DIN") (pintype "input"))
    )
    (net (code "80") (name "Net-(A26-2_DOUT)") (class "Default")
      (node (ref "A26") (pin "2-DOUT") (pinfunction "2_DOUT_2-DOUT") (pintype "output"))
      (node (ref "A27") (pin "4-DIN") (pinfunction "4_DIN_4-DIN") (pintype "input"))
    )
    (net (code "81") (name "Net-(A27-2_DOUT)") (class "Default")
      (node (ref "A27") (pin "2-DOUT") (pinfunction "2_DOUT_2-DOUT") (pintype "output"))
      (node (ref "A28") (pin "4-DIN") (pinfunction "4_DIN_4-DIN") (pintype "input"))
    )
    (net (code "82") (name "Net-(A28-2_DOUT)") (class "Default")
      (node (ref "A28") (pin "2-DOUT") (pinfunction "2_DOUT_2-DOUT") (pintype "output"))
      (node (ref "A29") (pin "4-DIN") (pinfunction "4_DIN_4-DIN") (pintype "input"))
    )
    (net (code "83") (name "Net-(A29-2_DOUT)") (class "Default")
      (node (ref "A29") (pin "2-DOUT") (pinfunction "2_DOUT_2-DOUT") (pintype "output"))
      (node (ref "A30") (pin "4-DIN") (pinfunction "4_DIN_4-DIN") (pintype "input"))
    )
    (net (code "84") (name "Net-(A30-2_DOUT)") (class "Default")
      (node (ref "A30") (pin "2-DOUT") (pinfunction "2_DOUT_2-DOUT") (pintype "output"))
      (node (ref "A31") (pin "4-DIN") (pinfunction "4_DIN_4-DIN") (pintype "input"))
    )
    (net (code "85") (name "Net-(A31-2_DOUT)") (class "Default")
      (node (ref "A31") (pin "2-DOUT") (pinfunction "2_DOUT_2-DOUT") (pintype "output"))
      (node (ref "A32") (pin "4-DIN") (pinfunction "4_DIN_4-DIN") (pintype "input"))
    )
    (net (code "86") (name "Net-(A32-2_DOUT)") (class "Default")
      (node (ref "A32") (pin "2-DOUT") (pinfunction "2_DOUT_2-DOUT") (pintype "output"))
      (node (ref "A33") (pin "4-DIN") (pinfunction "4_DIN_4-DIN") (pintype "input"))
    )
    (net (code "87") (name "Net-(A33-2_DOUT)") (class "Default")
      (node (ref "A33") (pin "2-DOUT") (pinfunction "2_DOUT_2-DOUT") (pintype "output"))
      (node (ref "A34") (pin "4-DIN") (pinfunction "4_DIN_4-DIN") (pintype "input"))
    )
    (net (code "88") (name "Net-(A34-2_DOUT)") (class "Default")
      (node (ref "A34") (pin "2-DOUT") (pinfunction "2_DOUT_2-DOUT") (pintype "output"))
      (node (ref "A35") (pin "4-DIN") (pinfunction "4_DIN_4-DIN") (pintype "input"))
    )
    (net (code "89") (name "Net-(A35-2_DOUT)") (class "Default")
      (node (ref "A35") (pin "2-DOUT") (pinfunction "2_DOUT_2-DOUT") (pintype "output"))
      (node (ref "A36") (pin "4-DIN") (pinfunction "4_DIN_4-DIN") (pintype "input"))
    )
    (net (code "90") (name "Net-(A36-2_DOUT)") (class "Default")
      (node (ref "A36") (pin "2-DOUT") (pinfunction "2_DOUT_2-DOUT") (pintype "output"))
      (node (ref "A37") (pin "4-DIN") (pinfunction "4_DIN_4-DIN") (pintype "input"))
    )
    (net (code "91") (name "Net-(A37-2_DOUT)") (class "Default")
      (node (ref "A37") (pin "2-DOUT") (pinfunction "2_DOUT_2-DOUT") (pintype "output"))
      (node (ref "A38") (pin "4-DIN") (pinfunction "4_DIN_4-DIN") (pintype "input"))
    )
    (net (code "92") (name "Net-(A38-2_DOUT)") (class "Default")
      (node (ref "A38") (pin "2-DOUT") (pinfunction "2_DOUT_2-DOUT") (pintype "output"))
      (node (ref "A39") (pin "4-DIN") (pinfunction "4_DIN_4-DIN") (pintype "input"))
    )
    (net (code "93") (name "Net-(A39-2_DOUT)") (class "Default")
      (node (ref "A39") (pin "2-DOUT") (pinfunction "2_DOUT_2-DOUT") (pintype "output"))
      (node (ref "A40") (pin "4-DIN") (pinfunction "4_DIN_4-DIN") (pintype "input"))
    )
    (net (code "94") (name "Net-(A40-2_DOUT)") (class "Default")
      (node (ref "A40") (pin "2-DOUT") (pinfunction "2_DOUT_2-DOUT") (pintype "output"))
      (node (ref "A41") (pin "4-DIN") (pinfunction "4_DIN_4-DIN") (pintype "input"))
    )
    (net (code "95") (name "Net-(A41-2_DOUT)") (class "Default")
      (node (ref "A41") (pin "2-DOUT") (pinfunction "2_DOUT_2-DOUT") (pintype "output"))
      (node (ref "A42") (pin "4-DIN") (pinfunction "4_DIN_4-DIN") (pintype "input"))
    )
    (net (code "96") (name "Net-(A42-2_DOUT)") (class "Default")
      (node (ref "A42") (pin "2-DOUT") (pinfunction "2_DOUT_2-DOUT") (pintype "output"))
      (node (ref "A43") (pin "4-DIN") (pinfunction "4_DIN_4-DIN") (pintype "input"))
    )
    (net (code "97") (name "Net-(A43-2_DOUT)") (class "Default")
      (node (ref "A43") (pin "2-DOUT") (pinfunction "2_DOUT_2-DOUT") (pintype "output"))
      (node (ref "I44") (pin "D") (pinfunction "D_D") (pintype "passive"))
    )
    (net (code "98") (name "Net-(M2-H)") (class "Default")
      (node (ref "M2") (pin "7") (pinfunction "H_7") (pintype "bidirectional"))
      (node (ref "R25") (pin "1") (pinfunction "1_1") (pintype "passive"))
    )
    (net (code "99") (name "Net-(M3-D)") (class "Default")
      (node (ref "M3") (pin "3") (pinfunction "D_3") (pintype "bidirectional"))
      (node (ref "R29") (pin "2") (pinfunction "2_2") (pintype "passive"))
    )
    (net (code "100") (name "Net-(M3-H)") (class "Default")
      (node (ref "M3") (pin "7") (pinfunction "H_7") (pintype "bidirectional"))
      (node (ref "R33") (pin "1") (pinfunction "1_1") (pintype "passive"))
    )
    (net (code "101") (name "Net-(M4-G)") (class "Default")
      (node (ref "M4") (pin "6") (pinfunction "G_6") (pintype "bidirectional"))
      (node (ref "R40") (pin "1") (pinfunction "1_1") (pintype "passive"))
    )
    (net (code "102") (name "Net-(M4-H)") (class "Default")
      (node (ref "M4") (pin "7") (pinfunction "H_7") (pintype "bidirectional"))
      (node (ref "R41") (pin "1") (pinfunction "1_1") (pintype "passive"))
    )
    (net (code "103") (name "Net-(M5-H)") (class "Default")
      (node (ref "M5") (pin "7") (pinfunction "H_7") (pintype "bidirectional"))
      (node (ref "R49") (pin "1") (pinfunction "1_1") (pintype "passive"))
    )
    (net (code "104") (name "SCK") (class "Default")
      (node (ref "KB_MATRIX") (pin "5") (pinfunction "5_5") (pintype "power_in"))
      (node (ref "M0") (pin "11") (pinfunction "SC/SCK_11") (pintype "bidirectional"))
      (node (ref "M1") (pin "11") (pinfunction "SC/SCK_11") (pintype "bidirectional"))
      (node (ref "M2") (pin "11") (pinfunction "SC/SCK_11") (pintype "bidirectional"))
      (node (ref "M3") (pin "11") (pinfunction "SC/SCK_11") (pintype "bidirectional"))
      (node (ref "M4") (pin "11") (pinfunction "SC/SCK_11") (pintype "bidirectional"))
      (node (ref "M5") (pin "11") (pinfunction "SC/SCK_11") (pintype "bidirectional"))
    )
    (net (code "105") (name "VCC_1") (class "Default")
      (node (ref "A1") (pin "1-VDD") (pinfunction "1_VDD_1-VDD") (pintype "power_in"))
      (node (ref "A1.5") (pin "1-VDD") (pinfunction "1_VDD_1-VDD") (pintype "power_in"))
      (node (ref "A10") (pin "1-VDD") (pinfunction "1_VDD_1-VDD") (pintype "power_in"))
      (node (ref "A11") (pin "1-VDD") (pinfunction "1_VDD_1-VDD") (pintype "power_in"))
      (node (ref "A12") (pin "1-VDD") (pinfunction "1_VDD_1-VDD") (pintype "power_in"))
      (node (ref "A13") (pin "1-VDD") (pinfunction "1_VDD_1-VDD") (pintype "power_in"))
      (node (ref "A14") (pin "1-VDD") (pinfunction "1_VDD_1-VDD") (pintype "power_in"))
      (node (ref "A15") (pin "1-VDD") (pinfunction "1_VDD_1-VDD") (pintype "power_in"))
      (node (ref "A16") (pin "1-VDD") (pinfunction "1_VDD_1-VDD") (pintype "power_in"))
      (node (ref "A17") (pin "1-VDD") (pinfunction "1_VDD_1-VDD") (pintype "power_in"))
      (node (ref "A18") (pin "1-VDD") (pinfunction "1_VDD_1-VDD") (pintype "power_in"))
      (node (ref "A19") (pin "1-VDD") (pinfunction "1_VDD_1-VDD") (pintype "power_in"))
      (node (ref "A2") (pin "1-VDD") (pinfunction "1_VDD_1-VDD") (pintype "power_in"))
      (node (ref "A20") (pin "1-VDD") (pinfunction "1_VDD_1-VDD") (pintype "power_in"))
      (node (ref "A21") (pin "1-VDD") (pinfunction "1_VDD_1-VDD") (pintype "power_in"))
      (node (ref "A22") (pin "1-VDD") (pinfunction "1_VDD_1-VDD") (pintype "power_in"))
      (node (ref "A23") (pin "1-VDD") (pinfunction "1_VDD_1-VDD") (pintype "power_in"))
      (node (ref "A24") (pin "1-VDD") (pinfunction "1_VDD_1-VDD") (pintype "power_in"))
      (node (ref "A25") (pin "1-VDD") (pinfunction "1_VDD_1-VDD") (pintype "power_in"))
      (node (ref "A26") (pin "1-VDD") (pinfunction "1_VDD_1-VDD") (pintype "power_in"))
      (node (ref "A27") (pin "1-VDD") (pinfunction "1_VDD_1-VDD") (pintype "power_in"))
      (node (ref "A28") (pin "1-VDD") (pinfunction "1_VDD_1-VDD") (pintype "power_in"))
      (node (ref "A29") (pin "1-VDD") (pinfunction "1_VDD_1-VDD") (pintype "power_in"))
      (node (ref "A3") (pin "1-VDD") (pinfunction "1_VDD_1-VDD") (pintype "power_in"))
      (node (ref "A30") (pin "1-VDD") (pinfunction "1_VDD_1-VDD") (pintype "power_in"))
      (node (ref "A31") (pin "1-VDD") (pinfunction "1_VDD_1-VDD") (pintype "power_in"))
      (node (ref "A32") (pin "1-VDD") (pinfunction "1_VDD_1-VDD") (pintype "power_in"))
      (node (ref "A33") (pin "1-VDD") (pinfunction "1_VDD_1-VDD") (pintype "power_in"))
      (node (ref "A34") (pin "1-VDD") (pinfunction "1_VDD_1-VDD") (pintype "power_in"))
      (node (ref "A35") (pin "1-VDD") (pinfunction "1_VDD_1-VDD") (pintype "power_in"))
      (node (ref "A36") (pin "1-VDD") (pinfunction "1_VDD_1-VDD") (pintype "power_in"))
      (node (ref "A37") (pin "1-VDD") (pinfunction "1_VDD_1-VDD") (pintype "power_in"))
      (node (ref "A38") (pin "1-VDD") (pinfunction "1_VDD_1-VDD") (pintype "power_in"))
      (node (ref "A39") (pin "1-VDD") (pinfunction "1_VDD_1-VDD") (pintype "power_in"))
      (node (ref "A4") (pin "1-VDD") (pinfunction "1_VDD_1-VDD") (pintype "power_in"))
      (node (ref "A40") (pin "1-VDD") (pinfunction "1_VDD_1-VDD") (pintype "power_in"))
      (node (ref "A41") (pin "1-VDD") (pinfunction "1_VDD_1-VDD") (pintype "power_in"))
      (node (ref "A42") (pin "1-VDD") (pinfunction "1_VDD_1-VDD") (pintype "power_in"))
      (node (ref "A43") (pin "1-VDD") (pinfunction "1_VDD_1-VDD") (pintype "power_in"))
      (node (ref "A5") (pin "1-VDD") (pinfunction "1_VDD_1-VDD") (pintype "power_in"))
      (node (ref "A6") (pin "1-VDD") (pinfunction "1_VDD_1-VDD") (pintype "power_in"))
      (node (ref "A7") (pin "1-VDD") (pinfunction "1_VDD_1-VDD") (pintype "power_in"))
      (node (ref "A8") (pin "1-VDD") (pinfunction "1_VDD_1-VDD") (pintype "power_in"))
      (node (ref "A9") (pin "1-VDD") (pinfunction "1_VDD_1-VDD") (pintype "power_in"))
      (node (ref "ARGB") (pin "2") (pinfunction "2_2") (pintype "passive"))
      (node (ref "CA1") (pin "1") (pinfunction "1_1") (pintype "passive"))
      (node (ref "CA11") (pin "1") (pinfunction "1_1") (pintype "passive"))
      (node (ref "CA13") (pin "1") (pinfunction "1_1") (pintype "passive"))
      (node (ref "CA15") (pin "1") (pinfunction "1_1") (pintype "passive"))
      (node (ref "CA17") (pin "1") (pinfunction "1_1") (pintype "passive"))
      (node (ref "CA19") (pin "1") (pinfunction "1_1") (pintype "passive"))
      (node (ref "CA21") (pin "1") (pinfunction "1_1") (pintype "passive"))
      (node (ref "CA23") (pin "1") (pinfunction "1_1") (pintype "passive"))
      (node (ref "CA25") (pin "1") (pinfunction "1_1") (pintype "passive"))
      (node (ref "CA27") (pin "1") (pinfunction "1_1") (pintype "passive"))
      (node (ref "CA29") (pin "1") (pinfunction "1_1") (pintype "passive"))
      (node (ref "CA3") (pin "1") (pinfunction "1_1") (pintype "passive"))
      (node (ref "CA31") (pin "1") (pinfunction "1_1") (pintype "passive"))
      (node (ref "CA33") (pin "1") (pinfunction "1_1") (pintype "passive"))
      (node (ref "CA35") (pin "1") (pinfunction "1_1") (pintype "passive"))
      (node (ref "CA37") (pin "1") (pinfunction "1_1") (pintype "passive"))
      (node (ref "CA39") (pin "1") (pinfunction "1_1") (pintype "passive"))
      (node (ref "CA41") (pin "1") (pinfunction "1_1") (pintype "passive"))
      (node (ref "CA43") (pin "1") (pinfunction "1_1") (pintype "passive"))
      (node (ref "CA5") (pin "1") (pinfunction "1_1") (pintype "passive"))
      (node (ref "CA6") (pin "1") (pinfunction "1_1") (pintype "passive"))
      (node (ref "CA7") (pin "1") (pinfunction "1_1") (pintype "passive"))
      (node (ref "CA9") (pin "1") (pinfunction "1_1") (pintype "passive"))
      (node (ref "I44") (pin "V") (pinfunction "V_V") (pintype "power_in"))
    )
    (net (code "106") (name "VCC_2") (class "Default")
      (node (ref "C1") (pin "1") (pinfunction "1_1") (pintype "passive"))
      (node (ref "C2") (pin "1") (pinfunction "1_1") (pintype "passive"))
      (node (ref "C3") (pin "1") (pinfunction "1_1") (pintype "passive"))
      (node (ref "C4") (pin "1") (pinfunction "1_1") (pintype "passive"))
      (node (ref "C5") (pin "1") (pinfunction "1_1") (pintype "passive"))
      (node (ref "C6") (pin "1") (pinfunction "1_1") (pintype "passive"))
      (node (ref "KB_MATRIX") (pin "2") (pinfunction "2_2") (pintype "passive"))
      (node (ref "M0") (pin "16") (pinfunction "VCC_16") (pintype "bidirectional"))
      (node (ref "M1") (pin "16") (pinfunction "VCC_16") (pintype "bidirectional"))
      (node (ref "M2") (pin "16") (pinfunction "VCC_16") (pintype "bidirectional"))
      (node (ref "M3") (pin "16") (pinfunction "VCC_16") (pintype "bidirectional"))
      (node (ref "M4") (pin "16") (pinfunction "VCC_16") (pintype "bidirectional"))
      (node (ref "M5") (pin "16") (pinfunction "VCC_16") (pintype "bidirectional"))
      (node (ref "R1") (pin "2") (pinfunction "2_2") (pintype "passive"))
      (node (ref "SW_A") (pin "2@1") (pinfunction "S_2@1") (pintype "passive"))
      (node (ref "SW_A") (pin "2@2") (pinfunction "S_2@2") (pintype "passive"))
      (node (ref "SW_B") (pin "2@1") (pinfunction "S_2@1") (pintype "passive"))
      (node (ref "SW_B") (pin "2@2") (pinfunction "S_2@2") (pintype "passive"))
      (node (ref "SW_BSP") (pin "2@1") (pinfunction "S_2@1") (pintype "passive"))
      (node (ref "SW_BSP") (pin "2@2") (pinfunction "S_2@2") (pintype "passive"))
      (node (ref "SW_C") (pin "2@1") (pinfunction "S_2@1") (pintype "passive"))
      (node (ref "SW_C") (pin "2@2") (pinfunction "S_2@2") (pintype "passive"))
      (node (ref "SW_D") (pin "2@1") (pinfunction "S_2@1") (pintype "passive"))
      (node (ref "SW_D") (pin "2@2") (pinfunction "S_2@2") (pintype "passive"))
      (node (ref "SW_DEL") (pin "2@1") (pinfunction "S_2@1") (pintype "passive"))
      (node (ref "SW_DEL") (pin "2@2") (pinfunction "S_2@2") (pintype "passive"))
      (node (ref "SW_DN") (pin "2@1") (pinfunction "S_2@1") (pintype "passive"))
      (node (ref "SW_DN") (pin "2@2") (pinfunction "S_2@2") (pintype "passive"))
      (node (ref "SW_E") (pin "2@1") (pinfunction "S_2@1") (pintype "passive"))
      (node (ref "SW_E") (pin "2@2") (pinfunction "S_2@2") (pintype "passive"))
      (node (ref "SW_ENT") (pin "2@1") (pinfunction "S_2@1") (pintype "passive"))
      (node (ref "SW_ENT") (pin "2@2") (pinfunction "S_2@2") (pintype "passive"))
      (node (ref "SW_ESC") (pin "2@1") (pinfunction "S_2@1") (pintype "passive"))
      (node (ref "SW_ESC") (pin "2@2") (pinfunction "S_2@2") (pintype "passive"))
      (node (ref "SW_F") (pin "2@1") (pinfunction "S_2@1") (pintype "passive"))
      (node (ref "SW_F") (pin "2@2") (pinfunction "S_2@2") (pintype "passive"))
      (node (ref "SW_G") (pin "2@1") (pinfunction "S_2@1") (pintype "passive"))
      (node (ref "SW_G") (pin "2@2") (pinfunction "S_2@2") (pintype "passive"))
      (node (ref "SW_H") (pin "2@1") (pinfunction "S_2@1") (pintype "passive"))
      (node (ref "SW_H") (pin "2@2") (pinfunction "S_2@2") (pintype "passive"))
      (node (ref "SW_I") (pin "2@1") (pinfunction "S_2@1") (pintype "passive"))
      (node (ref "SW_I") (pin "2@2") (pinfunction "S_2@2") (pintype "passive"))
      (node (ref "SW_J") (pin "2@1") (pinfunction "S_2@1") (pintype "passive"))
      (node (ref "SW_J") (pin "2@2") (pinfunction "S_2@2") (pintype "passive"))
      (node (ref "SW_K") (pin "2@1") (pinfunction "S_2@1") (pintype "passive"))
      (node (ref "SW_K") (pin "2@2") (pinfunction "S_2@2") (pintype "passive"))
      (node (ref "SW_L") (pin "2@1") (pinfunction "S_2@1") (pintype "passive"))
      (node (ref "SW_L") (pin "2@2") (pinfunction "S_2@2") (pintype "passive"))
      (node (ref "SW_LA") (pin "2@1") (pinfunction "S_2@1") (pintype "passive"))
      (node (ref "SW_LA") (pin "2@2") (pinfunction "S_2@2") (pintype "passive"))
      (node (ref "SW_LC") (pin "2@1") (pinfunction "S_2@1") (pintype "passive"))
      (node (ref "SW_LC") (pin "2@2") (pinfunction "S_2@2") (pintype "passive"))
      (node (ref "SW_LF") (pin "2@1") (pinfunction "S_2@1") (pintype "passive"))
      (node (ref "SW_LF") (pin "2@2") (pinfunction "S_2@2") (pintype "passive"))
      (node (ref "SW_LS") (pin "2@1") (pinfunction "S_2@1") (pintype "passive"))
      (node (ref "SW_LS") (pin "2@2") (pinfunction "S_2@2") (pintype "passive"))
      (node (ref "SW_LW") (pin "2@1") (pinfunction "S_2@1") (pintype "passive"))
      (node (ref "SW_LW") (pin "2@2") (pinfunction "S_2@2") (pintype "passive"))
      (node (ref "SW_M") (pin "2@1") (pinfunction "S_2@1") (pintype "passive"))
      (node (ref "SW_M") (pin "2@2") (pinfunction "S_2@2") (pintype "passive"))
      (node (ref "SW_N") (pin "2@1") (pinfunction "S_2@1") (pintype "passive"))
      (node (ref "SW_N") (pin "2@2") (pinfunction "S_2@2") (pintype "passive"))
      (node (ref "SW_O") (pin "2@1") (pinfunction "S_2@1") (pintype "passive"))
      (node (ref "SW_O") (pin "2@2") (pinfunction "S_2@2") (pintype "passive"))
      (node (ref "SW_P") (pin "2@1") (pinfunction "S_2@1") (pintype "passive"))
      (node (ref "SW_P") (pin "2@2") (pinfunction "S_2@2") (pintype "passive"))
      (node (ref "SW_Q") (pin "2@1") (pinfunction "S_2@1") (pintype "passive"))
      (node (ref "SW_Q") (pin "2@2") (pinfunction "S_2@2") (pintype "passive"))
      (node (ref "SW_R") (pin "2@1") (pinfunction "S_2@1") (pintype "passive"))
      (node (ref "SW_R") (pin "2@2") (pinfunction "S_2@2") (pintype "passive"))
      (node (ref "SW_RS") (pin "2@1") (pinfunction "S_2@1") (pintype "passive"))
      (node (ref "SW_RS") (pin "2@2") (pinfunction "S_2@2") (pintype "passive"))
      (node (ref "SW_RT") (pin "2@1") (pinfunction "S_2@1") (pintype "passive"))
      (node (ref "SW_RT") (pin "2@2") (pinfunction "S_2@2") (pintype "passive"))
      (node (ref "SW_S") (pin "2@1") (pinfunction "S_2@1") (pintype "passive"))
      (node (ref "SW_S") (pin "2@2") (pinfunction "S_2@2") (pintype "passive"))
      (node (ref "SW_SPC_1") (pin "2@1") (pinfunction "S_2@1") (pintype "passive"))
      (node (ref "SW_SPC_1") (pin "2@2") (pinfunction "S_2@2") (pintype "passive"))
      (node (ref "SW_SPC_2") (pin "2@1") (pinfunction "S_2@1") (pintype "passive"))
      (node (ref "SW_SPC_2") (pin "2@2") (pinfunction "S_2@2") (pintype "passive"))
      (node (ref "SW_T") (pin "2@1") (pinfunction "S_2@1") (pintype "passive"))
      (node (ref "SW_T") (pin "2@2") (pinfunction "S_2@2") (pintype "passive"))
      (node (ref "SW_TAB") (pin "2@1") (pinfunction "S_2@1") (pintype "passive"))
      (node (ref "SW_TAB") (pin "2@2") (pinfunction "S_2@2") (pintype "passive"))
      (node (ref "SW_U") (pin "2@1") (pinfunction "S_2@1") (pintype "passive"))
      (node (ref "SW_U") (pin "2@2") (pinfunction "S_2@2") (pintype "passive"))
      (node (ref "SW_UP") (pin "2@1") (pinfunction "S_2@1") (pintype "passive"))
      (node (ref "SW_UP") (pin "2@2") (pinfunction "S_2@2") (pintype "passive"))
      (node (ref "SW_V") (pin "2@1") (pinfunction "S_2@1") (pintype "passive"))
      (node (ref "SW_V") (pin "2@2") (pinfunction "S_2@2") (pintype "passive"))
      (node (ref "SW_W") (pin "2@1") (pinfunction "S_2@1") (pintype "passive"))
      (node (ref "SW_W") (pin "2@2") (pinfunction "S_2@2") (pintype "passive"))
      (node (ref "SW_X") (pin "2@1") (pinfunction "S_2@1") (pintype "passive"))
      (node (ref "SW_X") (pin "2@2") (pinfunction "S_2@2") (pintype "passive"))
      (node (ref "SW_Y") (pin "2@1") (pinfunction "S_2@1") (pintype "passive"))
      (node (ref "SW_Y") (pin "2@2") (pinfunction "S_2@2") (pintype "passive"))
      (node (ref "SW_Z") (pin "2@1") (pinfunction "S_2@1") (pintype "passive"))
      (node (ref "SW_Z") (pin "2@2") (pinfunction "S_2@2") (pintype "passive"))
    )
  )
)
